# Micromouse_1_2.net
KiCad netlist of a schematic drawn in Altium Designer
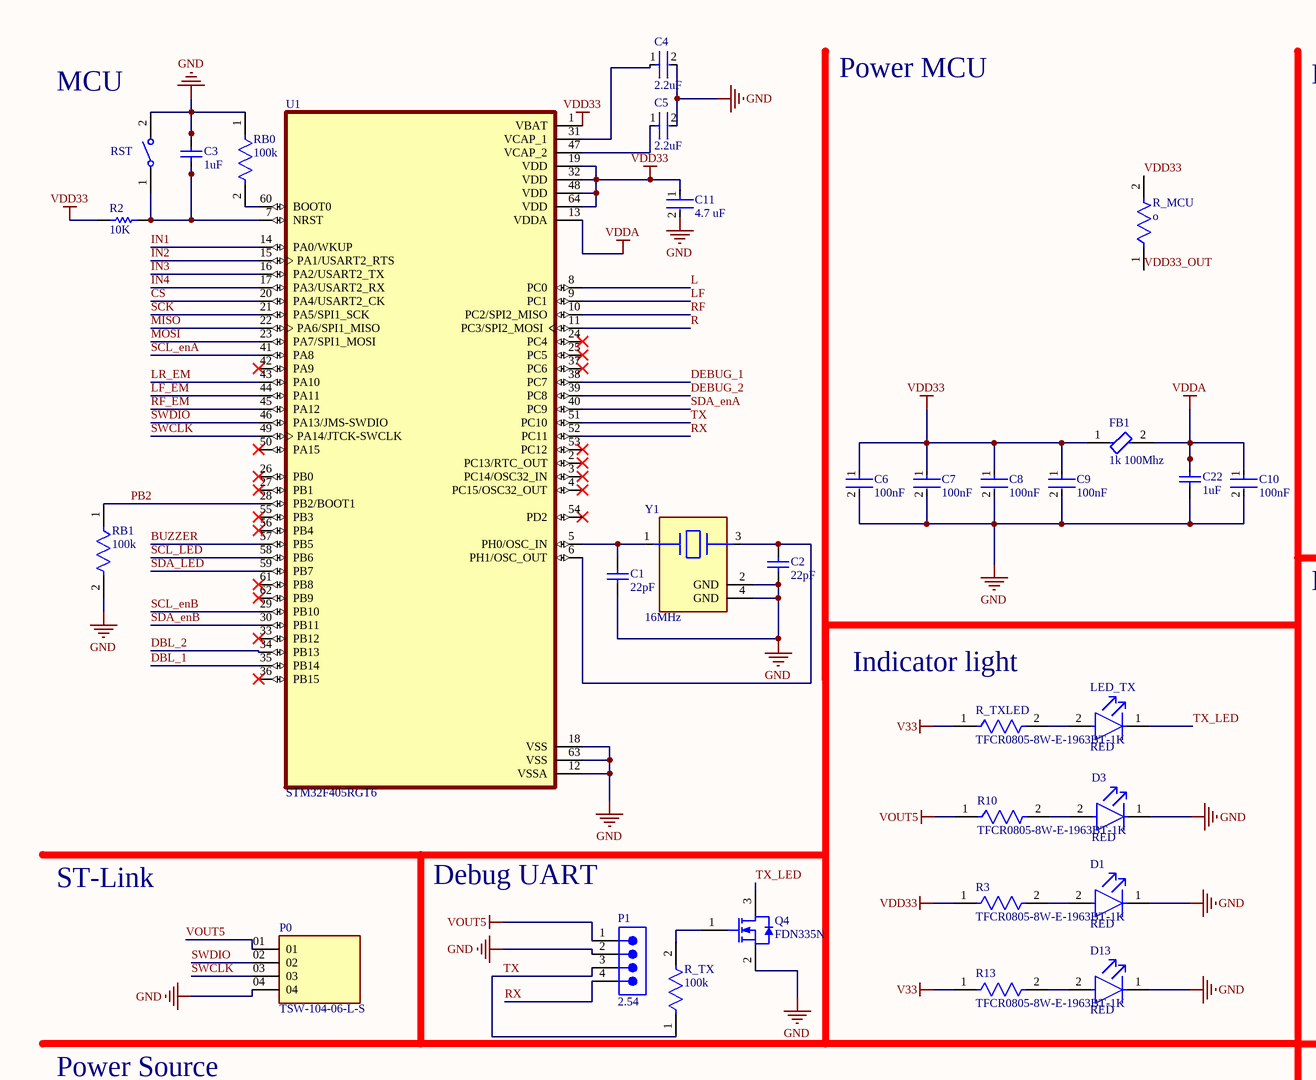
[diagram p0: Micromouse_1_2.SchDoc, top left]
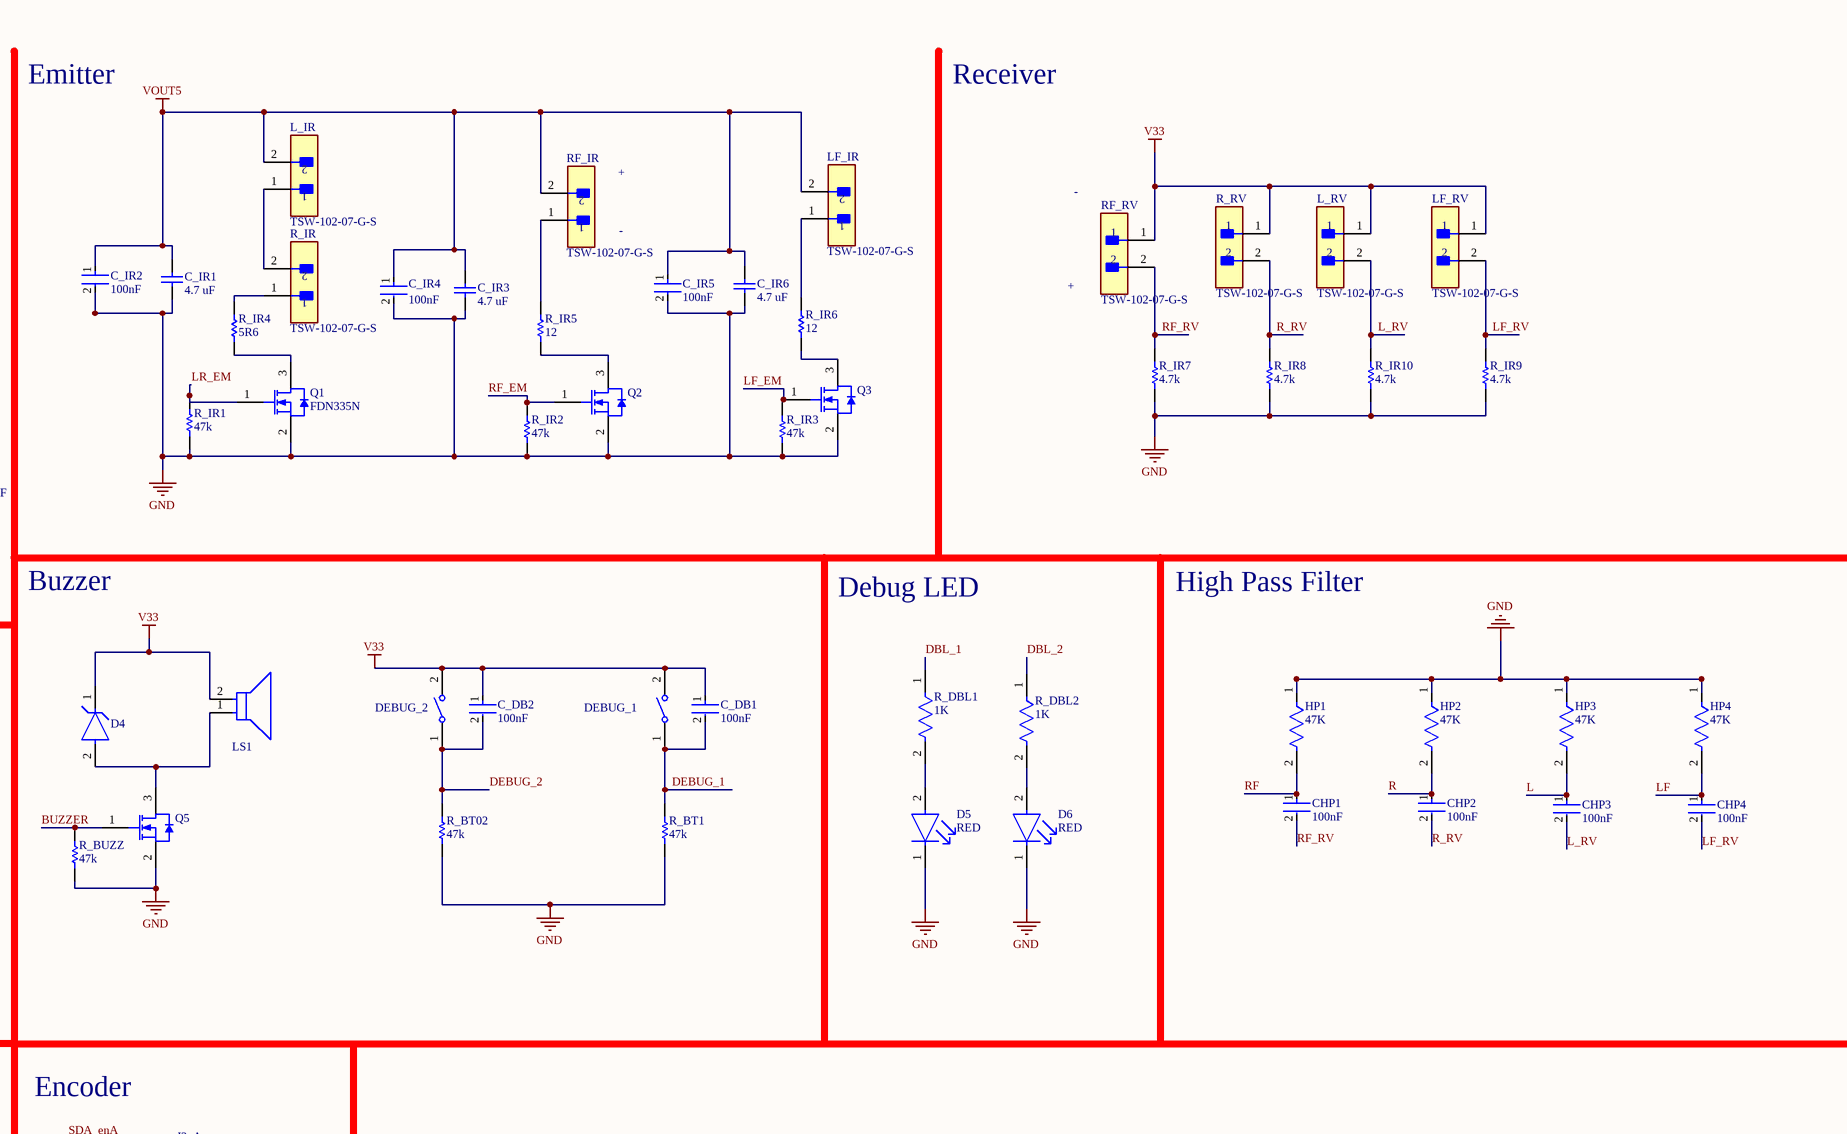
[diagram p1: Micromouse_1_2.SchDoc, top right]
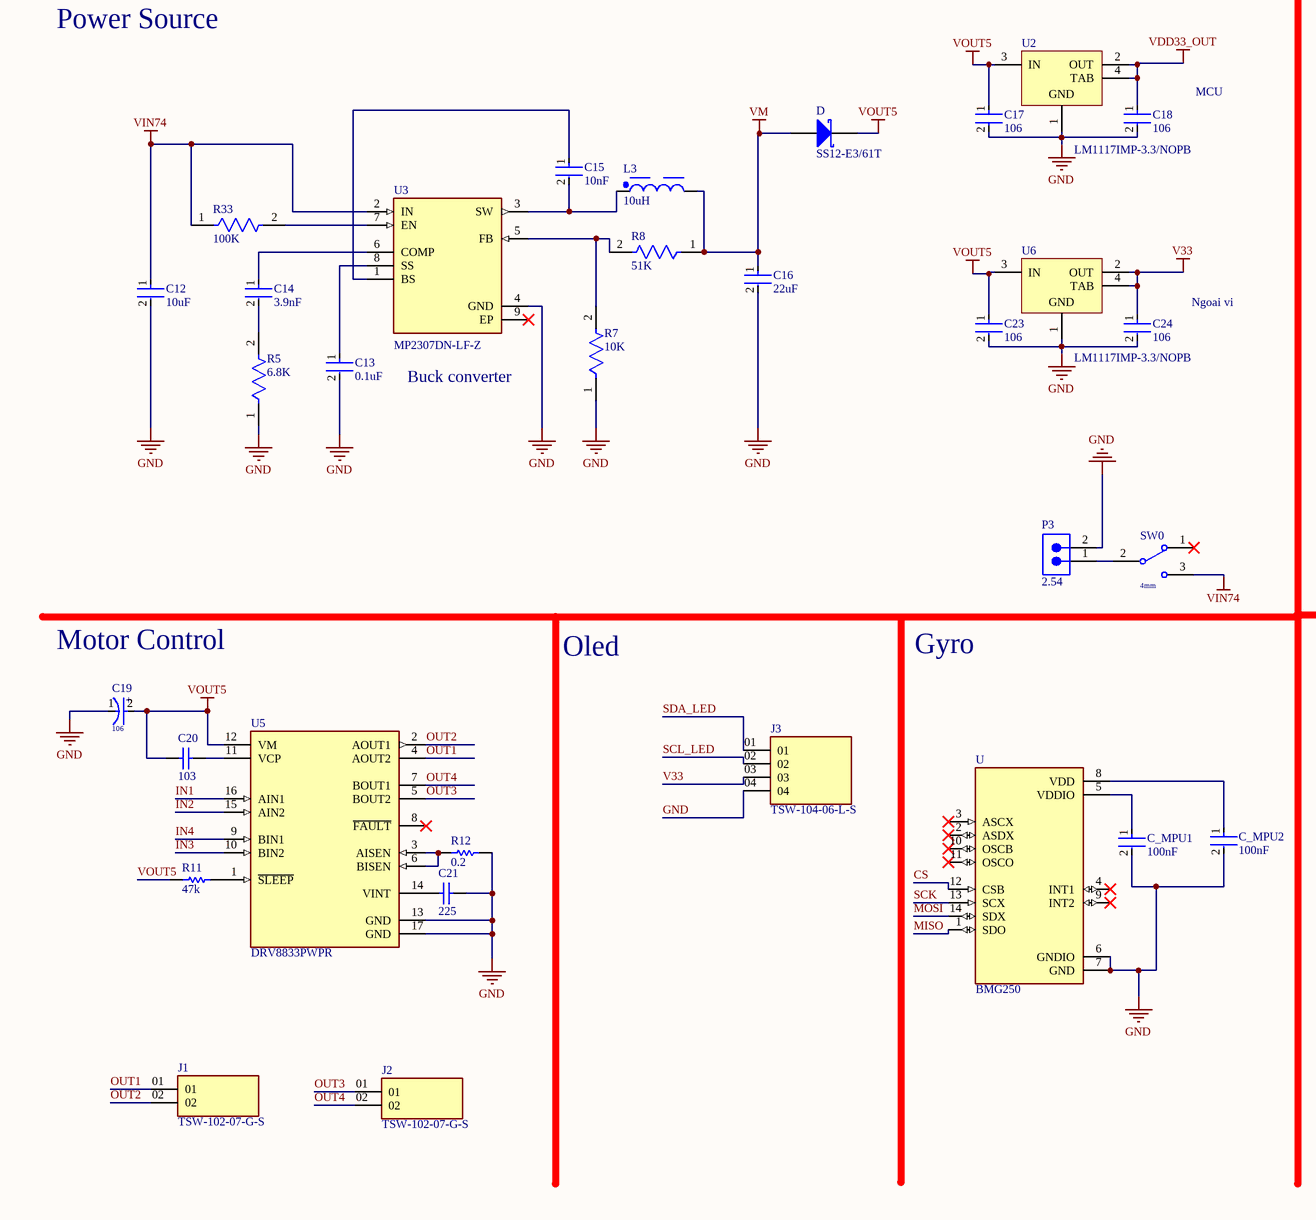
[diagram p2: Micromouse_1_2.SchDoc, bottom left]
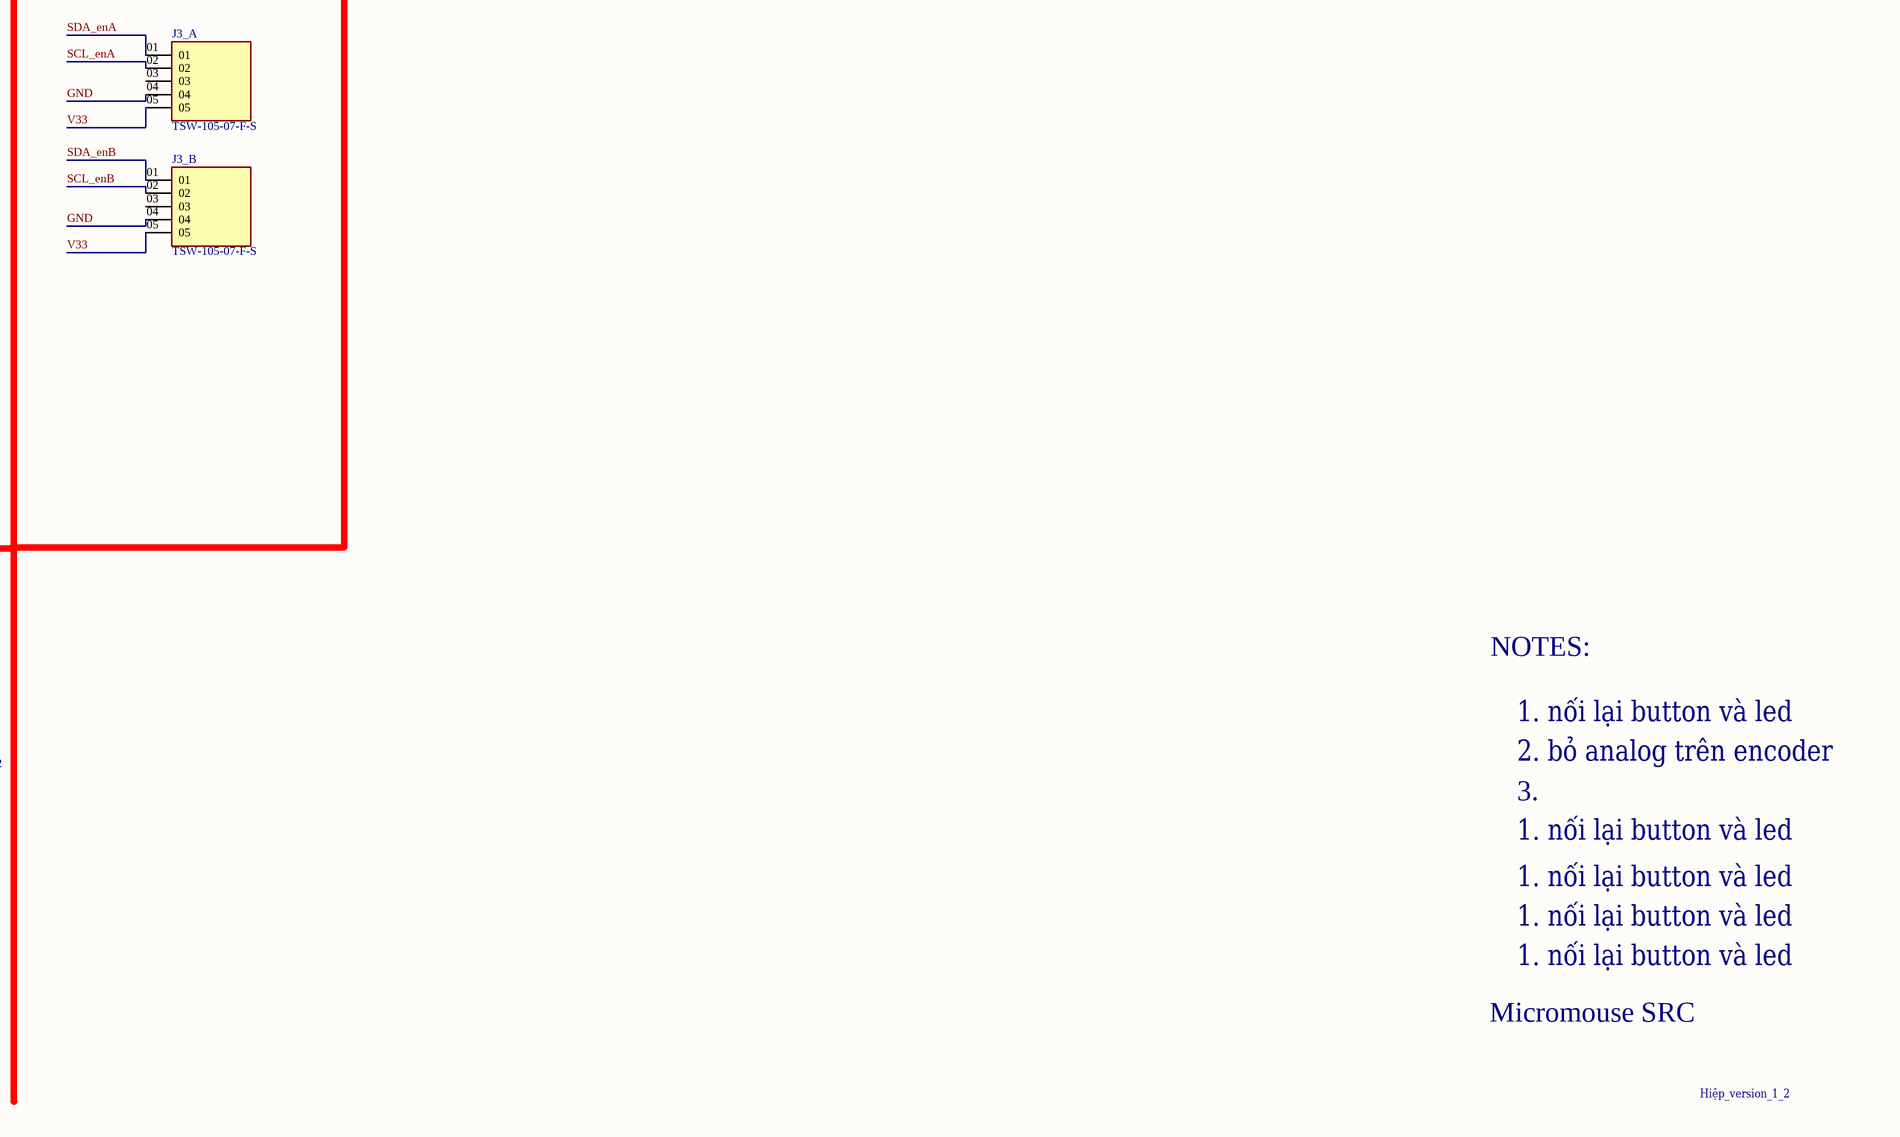
[diagram p3: Micromouse_1_2.SchDoc, bottom right]

(export (version "E")
  (design (tool "Eeschema 10.0.6"))
  (components
    (comp (ref "C1")
      (value "22pF")
      (footprint "CAPC1608X92X38ML15T08")
      (fields (field (name "PART NUMBER") "VJ0603A220FXBAC") (field (name "MANUFACTURER") "Vitramon"))
      (libsource (lib "Altium Content Vault") (part "CAP"))
    )
    (comp (ref "C2")
      (value "22pF")
      (footprint "CAPC1608X92X38ML15T08")
      (fields (field (name "PART NUMBER") "VJ0603A220FXBAC") (field (name "MANUFACTURER") "Vitramon"))
      (libsource (lib "Altium Content Vault") (part "CAP"))
    )
    (comp (ref "C3")
      (value "1uF")
      (footprint "CAPC1608X90X35NL15T15")
      (fields
        (field (name "PART NUMBER") "0603YD105MAT2A")
        (field (name "MANUFACTURER") "AVX Interconnect / Elco")
      )
      (libsource (lib "Altium Content Vault") (part "CAP"))
    )
    (comp (ref "C4")
      (value "2.2uF")
      (footprint "FP-CL21-IPC_B")
      (description "CL21 Series 0805 2.2uF 16V -20/+80% Tolerance Y5V Multilayer Ceramic Chip Capacitor")
      (fields (field (name "TOLERANCE") "80%") (field (name "VOLTAGE") "10V"))
      (libsource (lib "Altium Content Vault") (part "b4654b650e69147ec39a6b967a45e02"))
    )
    (comp (ref "C5")
      (value "2.2uF")
      (footprint "FP-CL21-IPC_B")
      (description "CL21 Series 0805 2.2uF 16V -20/+80% Tolerance Y5V Multilayer Ceramic Chip Capacitor")
      (fields (field (name "TOLERANCE") "80%") (field (name "VOLTAGE") "10V"))
      (libsource (lib "Altium Content Vault") (part "b4654b650e69147ec39a6b967a45e02"))
    )
    (comp (ref "C6")
      (value "100nF")
      (footprint "FP-CL10-IPC_C")
      (description "Cap Ceramic 100nF 25V X7R ±10% Pad SMD 0603 +125°C T/R")
      (fields (field (name "TOLERANCE") "10%"))
      (libsource (lib "Altium Content Vault") (part "b4654b650e69147ec39a6b967a45e02"))
    )
    (comp (ref "C7")
      (value "100nF")
      (footprint "FP-CL10-IPC_C")
      (description "Cap Ceramic 100nF 25V X7R ±10% Pad SMD 0603 +125°C T/R")
      (fields (field (name "TOLERANCE") "10%"))
      (libsource (lib "Altium Content Vault") (part "b4654b650e69147ec39a6b967a45e02"))
    )
    (comp (ref "C8")
      (value "100nF")
      (footprint "FP-CL10-IPC_C")
      (description "Cap Ceramic 100nF 25V X7R ±10% Pad SMD 0603 +125°C T/R")
      (fields (field (name "TOLERANCE") "10%"))
      (libsource (lib "Altium Content Vault") (part "b4654b650e69147ec39a6b967a45e02"))
    )
    (comp (ref "C9")
      (value "100nF")
      (footprint "FP-CL10-IPC_C")
      (description "Cap Ceramic 100nF 25V X7R ±10% Pad SMD 0603 +125°C T/R")
      (fields (field (name "TOLERANCE") "10%"))
      (libsource (lib "Altium Content Vault") (part "b4654b650e69147ec39a6b967a45e02"))
    )
    (comp (ref "C10")
      (value "100nF")
      (footprint "FP-CL10-IPC_C")
      (description "Cap Ceramic 100nF 25V X7R ±10% Pad SMD 0603 +125°C T/R")
      (fields (field (name "TOLERANCE") "10%"))
      (libsource (lib "Altium Content Vault") (part "b4654b650e69147ec39a6b967a45e02"))
    )
    (comp (ref "C11")
      (value "4.7 uF")
      (footprint "FP-C0603-CG-MFG")
      (description "CAP CER 4.7UF 6.3V X5R 0603")
      (fields (field (name "TOLERANCE") "10%") (field (name "MANUFACTURER") "Kemet"))
      (libsource (lib "Altium Content Vault") (part "11868f565c42a9108669ba33697ecf6"))
    )
    (comp (ref "C12")
      (value "10uF")
      (footprint "FP-C1206C-EB-MFG")
      (description "C1206 10 uF C0G 5.00% 50 V")
      (fields
        (field (name "MANUFACTURER PART NUMBER") "C1206C100J5GAC")
        (field (name "MANUFACTURER") "KEMET")
      )
      (libsource (lib "Altium Content Vault") (part "b4654b650e69147ec39a6b967a45e02"))
    )
    (comp (ref "C13")
      (value "0.1uF")
      (footprint "FP-C1206C-EB-MFG")
      (description "C1206 10 pF C0G 5.00% 50 V")
      (fields
        (field (name "MANUFACTURER PART NUMBER") "C1206C100J5GAC")
        (field (name "MANUFACTURER") "KEMET")
      )
      (libsource (lib "Altium Content Vault") (part "b4654b650e69147ec39a6b967a45e02"))
    )
    (comp (ref "C14")
      (value "3.9nF")
      (footprint "FP-C1206C-EB-MFG")
      (description "C1206 4.8nF C0G 5.00% 50 V")
      (fields
        (field (name "MANUFACTURER PART NUMBER") "C1206C100J5GAC")
        (field (name "MANUFACTURER") "KEMET")
      )
      (libsource (lib "Altium Content Vault") (part "b4654b650e69147ec39a6b967a45e02"))
    )
    (comp (ref "C15")
      (value "10nF")
      (footprint "FP-C1206C-EB-MFG")
      (description "C1206 10 pF C0G 5.00% 50 V")
      (fields
        (field (name "MANUFACTURER PART NUMBER") "C1206C100J5GAC")
        (field (name "MANUFACTURER") "KEMET")
      )
      (libsource (lib "Altium Content Vault") (part "b4654b650e69147ec39a6b967a45e02"))
    )
    (comp (ref "C16")
      (value "22uF")
      (footprint "FP-C1206C-EB-MFG")
      (description "C1206 10 pF C0G 5.00% 50 V")
      (fields
        (field (name "MANUFACTURER PART NUMBER") "C1206C100J5GAC")
        (field (name "MANUFACTURER") "KEMET")
      )
      (libsource (lib "Altium Content Vault") (part "b4654b650e69147ec39a6b967a45e02"))
    )
    (comp (ref "C17")
      (value "106")
      (footprint "FP-GRT31C-0_2-IPC_A")
      (description "Multi-Layer Ceramic Capacitor 10uF 50V X5R ±10% 1206 Emboss T/R")
      (fields (field (name "TOLERANCE") "10%"))
      (libsource (lib "Altium Content Vault") (part "02cd4be3c70576c341d710602a673aa"))
    )
    (comp (ref "C18")
      (value "106")
      (footprint "FP-GRT31C-0_2-IPC_A")
      (description "Multi-Layer Ceramic Capacitor 10uF 50V X5R ±10% 1206 Emboss T/R")
      (fields (field (name "TOLERANCE") "10%"))
      (libsource (lib "Altium Content Vault") (part "02cd4be3c70576c341d710602a673aa"))
    )
    (comp (ref "C19")
      (value "106")
      (footprint "FP-T491C-MFG")
      (description "CAP TANT 10UF 10% 25V 2312")
      (fields (field (name "TOLERANCE") "10%") (field (name "MANUFACTURER PART NUMBER") "T491C106K025AT"))
      (libsource (lib "Altium Content Vault") (part "203bc49f2ac43e59fd269a8c329ed05"))
    )
    (comp (ref "C20")
      (value "103")
      (footprint "CAPC2013X88X50LL20T25")
      (fields (field (name "MANUFACTURER") "Kemet") (field (name "PART NUMBER") "C0805C103K5RACTU"))
      (libsource (lib "Altium Content Vault") (part "CAP"))
    )
    (comp (ref "C21")
      (value "225")
      (footprint "CAPC3216X180X50LL20T25")
      (description "Chip Capacitor, 2.2 uF, +/- 10%, 50 V, -55 to 125 degC, 1206 (3216 Metric), RoHS, Tape and Reel")
      (fields (field (name "MANUFACTURER") "Kemet") (field (name "TOLERANCE") "10%"))
      (libsource (lib "Altium Content Vault") (part "CAP-NP-2"))
    )
    (comp (ref "C22")
      (value "1uF")
      (footprint "CAPC1608X90X35NL15T15")
      (fields
        (field (name "PART NUMBER") "0603YD105MAT2A")
        (field (name "MANUFACTURER") "AVX Interconnect / Elco")
      )
      (libsource (lib "Altium Content Vault") (part "CAP"))
    )
    (comp (ref "C23")
      (value "106")
      (footprint "FP-GRT31C-0_2-IPC_A")
      (description "Multi-Layer Ceramic Capacitor 10uF 50V X5R ±10% 1206 Emboss T/R")
      (fields (field (name "TOLERANCE") "10%"))
      (libsource (lib "Altium Content Vault") (part "02cd4be3c70576c341d710602a673aa"))
    )
    (comp (ref "C24")
      (value "106")
      (footprint "FP-GRT31C-0_2-IPC_A")
      (description "Multi-Layer Ceramic Capacitor 10uF 50V X5R ±10% 1206 Emboss T/R")
      (fields (field (name "TOLERANCE") "10%"))
      (libsource (lib "Altium Content Vault") (part "02cd4be3c70576c341d710602a673aa"))
    )
    (comp (ref "CHP1")
      (value "100nF")
      (footprint "FP-CL10-IPC_C")
      (description "Cap Ceramic 100nF 25V X7R ±10% Pad SMD 0603 +125°C T/R")
      (fields (field (name "TOLERANCE") "10%"))
      (libsource (lib "Altium Content Vault") (part "b4654b650e69147ec39a6b967a45e02"))
    )
    (comp (ref "CHP2")
      (value "100nF")
      (footprint "FP-CL10-IPC_C")
      (description "Cap Ceramic 100nF 25V X7R ±10% Pad SMD 0603 +125°C T/R")
      (fields (field (name "TOLERANCE") "10%"))
      (libsource (lib "Altium Content Vault") (part "b4654b650e69147ec39a6b967a45e02"))
    )
    (comp (ref "CHP3")
      (value "100nF")
      (footprint "FP-CL10-IPC_C")
      (description "Cap Ceramic 100nF 25V X7R ±10% Pad SMD 0603 +125°C T/R")
      (fields (field (name "TOLERANCE") "10%"))
      (libsource (lib "Altium Content Vault") (part "b4654b650e69147ec39a6b967a45e02"))
    )
    (comp (ref "CHP4")
      (value "100nF")
      (footprint "FP-CL10-IPC_C")
      (description "Cap Ceramic 100nF 25V X7R ±10% Pad SMD 0603 +125°C T/R")
      (fields (field (name "TOLERANCE") "10%"))
      (libsource (lib "Altium Content Vault") (part "b4654b650e69147ec39a6b967a45e02"))
    )
    (comp (ref "C_DB1")
      (value "100nF")
      (footprint "FP-CL10-IPC_C")
      (description "Cap Ceramic 100nF 25V X7R ±10% Pad SMD 0603 +125°C T/R")
      (fields (field (name "TOLERANCE") "10%"))
      (libsource (lib "Altium Content Vault") (part "b4654b650e69147ec39a6b967a45e02"))
    )
    (comp (ref "C_DB2")
      (value "100nF")
      (footprint "FP-CL10-IPC_C")
      (description "Cap Ceramic 100nF 25V X7R ±10% Pad SMD 0603 +125°C T/R")
      (fields (field (name "TOLERANCE") "10%"))
      (libsource (lib "Altium Content Vault") (part "b4654b650e69147ec39a6b967a45e02"))
    )
    (comp (ref "C_IR1")
      (value "4.7 uF")
      (footprint "CAPC2013X145X48ML20T23")
      (fields (field (name "MANUFACTURER") "Vitramon") (field (name "PART NUMBER") "VJ0805Y682KXAMT"))
      (libsource (lib "Altium Content Vault") (part "CAP"))
    )
    (comp (ref "C_IR2")
      (value "100nF")
      (footprint "FP-CL10-IPC_C")
      (description "Cap Ceramic 100nF 25V X7R ±10% Pad SMD 0603 +125°C T/R")
      (fields (field (name "TOLERANCE") "10%"))
      (libsource (lib "Altium Content Vault") (part "b4654b650e69147ec39a6b967a45e02"))
    )
    (comp (ref "C_IR3")
      (value "4.7 uF")
      (footprint "CAPC2013X145X48ML20T23")
      (fields (field (name "MANUFACTURER") "Vitramon") (field (name "PART NUMBER") "VJ0805Y682KXAMT"))
      (libsource (lib "Altium Content Vault") (part "CAP"))
    )
    (comp (ref "C_IR4")
      (value "100nF")
      (footprint "FP-CL10-IPC_C")
      (description "Cap Ceramic 100nF 25V X7R ±10% Pad SMD 0603 +125°C T/R")
      (fields (field (name "TOLERANCE") "10%"))
      (libsource (lib "Altium Content Vault") (part "b4654b650e69147ec39a6b967a45e02"))
    )
    (comp (ref "C_IR5")
      (value "100nF")
      (footprint "FP-CL10-IPC_C")
      (description "Cap Ceramic 100nF 25V X7R ±10% Pad SMD 0603 +125°C T/R")
      (fields (field (name "TOLERANCE") "10%"))
      (libsource (lib "Altium Content Vault") (part "b4654b650e69147ec39a6b967a45e02"))
    )
    (comp (ref "C_IR6")
      (value "4.7 uF")
      (footprint "CAPC2013X145X48ML20T23")
      (fields (field (name "MANUFACTURER") "Vitramon") (field (name "PART NUMBER") "VJ0805Y682KXAMT"))
      (libsource (lib "Altium Content Vault") (part "CAP"))
    )
    (comp (ref "C_MPU1")
      (value "100nF")
      (footprint "FP-CL10-IPC_C")
      (description "Cap Ceramic 100nF 25V X7R ±10% Pad SMD 0603 +125°C T/R")
      (fields (field (name "TOLERANCE") "10%"))
      (libsource (lib "Altium Content Vault") (part "b4654b650e69147ec39a6b967a45e02"))
    )
    (comp (ref "C_MPU2")
      (value "100nF")
      (footprint "FP-CL10-IPC_C")
      (description "Cap Ceramic 100nF 25V X7R ±10% Pad SMD 0603 +125°C T/R")
      (fields (field (name "TOLERANCE") "10%"))
      (libsource (lib "Altium Content Vault") (part "b4654b650e69147ec39a6b967a45e02"))
    )
    (comp (ref "D")
      (value "SS12-E3/61T")
      (footprint "VISH-DO-214AC_V")
      (description "Schottky Barrier Rectifier, 20 V, 1 A, -65 to 150 degC, 2-Pin DO-214AC (SMA), RoHS, Tape and Reel")
      (fields (field (name "MANUFACTURER") "Vishay Semiconductor"))
      (libsource (lib "Nguyen Hai Son") (part "DSKY-AK-2"))
    )
    (comp (ref "D1")
      (value "RED")
      (footprint "FP-LTST-C190GKT-MFG")
      (description "LED GREEN CLEAR CHIP SMD")
      (fields (field (name "VOLTAGE") "2V"))
      (libsource (lib "Altium Content Vault") (part "8706943c75ba83719d021d2fdc84c58"))
    )
    (comp (ref "D3")
      (value "RED")
      (footprint "FP-LTST-C190GKT-MFG")
      (description "LED GREEN CLEAR CHIP SMD")
      (fields (field (name "VOLTAGE") "2V"))
      (libsource (lib "Altium Content Vault") (part "8706943c75ba83719d021d2fdc84c58"))
    )
    (comp (ref "D4")
      (value "MMSZ5232B")
      (footprint "FP-MA02A-MFG")
      (description "MMSZ5232B MMSZ523 Series 500 mW 5.6 V 10 mA SMT Half-Watt Zener Diode SOD-123")
      (fields (field (name "TOLERANCE") "5%"))
      (libsource (lib "Altium Content Vault") (part "f813f71cba58e380607f5dd3caf9714"))
    )
    (comp (ref "D5")
      (value "RED")
      (footprint "FP-LTST-C190GKT-MFG")
      (description "LED GREEN CLEAR CHIP SMD")
      (fields (field (name "VOLTAGE") "2V"))
      (libsource (lib "Altium Content Vault") (part "8706943c75ba83719d021d2fdc84c58"))
    )
    (comp (ref "D6")
      (value "RED")
      (footprint "FP-LTST-C190GKT-MFG")
      (description "LED GREEN CLEAR CHIP SMD")
      (fields (field (name "VOLTAGE") "2V"))
      (libsource (lib "Altium Content Vault") (part "8706943c75ba83719d021d2fdc84c58"))
    )
    (comp (ref "D13")
      (value "RED")
      (footprint "FP-LTST-C190GKT-MFG")
      (description "LED GREEN CLEAR CHIP SMD")
      (fields (field (name "VOLTAGE") "2V"))
      (libsource (lib "Altium Content Vault") (part "8706943c75ba83719d021d2fdc84c58"))
    )
    (comp (ref "DEBUG_1")
      (value "~")
      (footprint "TECO-FSMSMTR_V")
      (description "FSMSM Push Button Switch, 50 mA, -35 to 85 degC, 2-Pin SMD, RoHS, Tape and Reel")
      (fields (field (name "MANUFACTURER") "TE Connectivity"))
      (libsource (lib "Altium Content Vault") (part "SW-SPST-2_C"))
    )
    (comp (ref "DEBUG_2")
      (value "~")
      (footprint "TECO-FSMSMTR_V")
      (description "FSMSM Push Button Switch, 50 mA, -35 to 85 degC, 2-Pin SMD, RoHS, Tape and Reel")
      (fields (field (name "MANUFACTURER") "TE Connectivity"))
      (libsource (lib "Altium Content Vault") (part "SW-SPST-2_C"))
    )
    (comp (ref "FB1")
      (value "1k 100Mhz")
      (footprint "FP-BLM21-0_2-t0_85-e0_5-IPC_C")
      (description "Chip Ferrite Bead, 0805, 60Ω @ 100MHz, 0.02Ω, 25%, 1.9A")
      (libsource (lib "Altium Content Vault") (part "5f30dd21d616792df468990f7003faa"))
    )
    (comp (ref "HP1")
      (value "47K")
      (footprint "FP-CRCW0805-e3-IPC_A")
      (description "RES Thick Film, 1kΩ, 5%, 0.125W, 200ppm/°C, 0805")
      (fields (field (name "TOLERANCE") "5%"))
      (libsource (lib "Altium Content Vault") (part "1029c3af85768c4190bb7ad29bc67b5"))
    )
    (comp (ref "HP2")
      (value "47K")
      (footprint "FP-CRCW0805-e3-IPC_A")
      (description "RES Thick Film, 1kΩ, 5%, 0.125W, 200ppm/°C, 0805")
      (fields (field (name "TOLERANCE") "5%"))
      (libsource (lib "Altium Content Vault") (part "1029c3af85768c4190bb7ad29bc67b5"))
    )
    (comp (ref "HP3")
      (value "47K")
      (footprint "FP-CRCW0805-e3-IPC_A")
      (description "RES Thick Film, 1kΩ, 5%, 0.125W, 200ppm/°C, 0805")
      (fields (field (name "TOLERANCE") "5%"))
      (libsource (lib "Altium Content Vault") (part "1029c3af85768c4190bb7ad29bc67b5"))
    )
    (comp (ref "HP4")
      (value "47K")
      (footprint "FP-CRCW0805-e3-IPC_A")
      (description "RES Thick Film, 1kΩ, 5%, 0.125W, 200ppm/°C, 0805")
      (fields (field (name "TOLERANCE") "5%"))
      (libsource (lib "Altium Content Vault") (part "1029c3af85768c4190bb7ad29bc67b5"))
    )
    (comp (ref "J1")
      (value "TSW-102-07-G-S")
      (footprint "SAMTEC_TSW-102-07-G-S")
      (fields (field (name "MF") "Samtec"))
      (libsource (lib "TSW-102-07-G-S") (part "TSW-102-07-G-S"))
    )
    (comp (ref "J2")
      (value "TSW-102-07-G-S")
      (footprint "SAMTEC_TSW-102-07-G-S")
      (fields (field (name "MF") "Samtec"))
      (libsource (lib "TSW-102-07-G-S") (part "TSW-102-07-G-S"))
    )
    (comp (ref "J3")
      (value "TSW-104-06-L-S")
      (footprint "SAMTEC_TSW-104-06-L-S")
      (libsource (lib "Vũ Hiệp") (part "TSW-104-06-L-S"))
    )
    (comp (ref "J3_A")
      (value "TSW-105-07-F-S")
      (footprint "SAMTEC_TSW-105-07-F-S")
      (fields (field (name "MF") "Samtec"))
      (libsource (lib "Vũ Hiệp") (part "TSW-105-07-F-S"))
    )
    (comp (ref "J3_B")
      (value "TSW-105-07-F-S")
      (footprint "SAMTEC_TSW-105-07-F-S")
      (fields (field (name "MF") "Samtec"))
      (libsource (lib "Vũ Hiệp") (part "TSW-105-07-F-S"))
    )
    (comp (ref "L3")
      (value "10uH")
      (footprint "WE-TPC_5818")
      (fields (field (name "TOLERANCE") "30%"))
      (libsource (lib "Altium Content Vault") (part "Inductor - 2"))
    )
    (comp (ref "LED_TX")
      (value "RED")
      (footprint "FP-LTST-C190GKT-MFG")
      (description "LED GREEN CLEAR CHIP SMD")
      (fields (field (name "VOLTAGE") "2V"))
      (libsource (lib "Altium Content Vault") (part "8706943c75ba83719d021d2fdc84c58"))
    )
    (comp (ref "LF_IR")
      (value "TSW-102-07-G-S")
      (footprint "FP-TSW-102-07-G-S-MFG")
      (description "CONN HEADER VERT 2POS 2.54MM")
      (fields
        (field (name "MANUFACTURER") "Samtec")
        (field (name "OCTOPART") "https://octopart.com/tsw-102-07-g-s-samtec-272197")
      )
      (libsource (lib "") (part "3bc925449376181038e59eaffc5286c_1"))
    )
    (comp (ref "LF_RV")
      (value "TSW-102-07-G-S")
      (footprint "FP-TSW-102-07-G-S-MFG")
      (description "CONN HEADER VERT 2POS 2.54MM")
      (fields
        (field (name "MANUFACTURER") "Samtec")
        (field (name "OCTOPART") "https://octopart.com/tsw-102-07-g-s-samtec-272197")
      )
      (libsource (lib "Altium Content Vault") (part "3bc925449376181038e59eaffc5286c"))
    )
    (comp (ref "LS1")
      (value "MCKPX-G1203A-K4056")
      (footprint "FP-MCKPX-G1203A-K4056-MFG")
      (description "MAGNETIC BUZZER AND TRANSDUCER - More Details")
      (fields
        (field (name "MANUFACTURER") "Multicomp Pro")
        (field (name "OCTOPART") "https://octopart.com/mckpx-g1203a-k4056-multicomp-12157154")
      )
      (libsource (lib "Altium Content Vault") (part "1973c4b650225fd2ddacaff6b763965"))
    )
    (comp (ref "L_IR")
      (value "TSW-102-07-G-S")
      (footprint "FP-TSW-102-07-G-S-MFG")
      (description "CONN HEADER VERT 2POS 2.54MM")
      (fields
        (field (name "MANUFACTURER") "Samtec")
        (field (name "OCTOPART") "https://octopart.com/tsw-102-07-g-s-samtec-272197")
      )
      (libsource (lib "") (part "3bc925449376181038e59eaffc5286c_1"))
    )
    (comp (ref "L_RV")
      (value "TSW-102-07-G-S")
      (footprint "FP-TSW-102-07-G-S-MFG")
      (description "CONN HEADER VERT 2POS 2.54MM")
      (fields
        (field (name "MANUFACTURER") "Samtec")
        (field (name "OCTOPART") "https://octopart.com/tsw-102-07-g-s-samtec-272197")
      )
      (libsource (lib "Altium Content Vault") (part "3bc925449376181038e59eaffc5286c"))
    )
    (comp (ref "P0")
      (value "TSW-104-06-L-S")
      (footprint "SAMTEC_TSW-104-06-L-S")
      (libsource (lib "Vũ Hiệp") (part "TSW-104-06-L-S"))
    )
    (comp (ref "P1")
      (value "2.54")
      (footprint "61300411121")
      (libsource (lib "Altium Content Vault") (part "Header_Male_1R_04P"))
    )
    (comp (ref "P3")
      (value "2.54")
      (footprint "61300211121")
      (libsource (lib "Altium Content Vault") (part "Header_Male_1R_02P"))
    )
    (comp (ref "Q1")
      (value "FDN335N")
      (footprint "FAIR-SSOT3L-3_V")
      (fields (field (name "MANUFACTURER") "FairchildSemiconductor"))
      (libsource (lib "Altium Content Vault") (part "NEMOS-GSD-3"))
    )
    (comp (ref "Q2")
      (value "~")
      (footprint "FAIR-SSOT3L-3_V")
      (fields (field (name "MANUFACTURER") "FairchildSemiconductor"))
      (libsource (lib "Altium Content Vault") (part "NEMOS-GSD-3"))
    )
    (comp (ref "Q3")
      (value "~")
      (footprint "FAIR-SSOT3L-3_V")
      (fields (field (name "MANUFACTURER") "FairchildSemiconductor"))
      (libsource (lib "Altium Content Vault") (part "NEMOS-GSD-3"))
    )
    (comp (ref "Q4")
      (value "FDN335N")
      (footprint "FAIR-SSOT3L-3_V")
      (fields (field (name "MANUFACTURER") "FairchildSemiconductor"))
      (libsource (lib "Altium Content Vault") (part "NEMOS-GSD-3"))
    )
    (comp (ref "Q5")
      (value "~")
      (footprint "FAIR-SSOT3L-3_V")
      (fields (field (name "MANUFACTURER") "FairchildSemiconductor"))
      (libsource (lib "Altium Content Vault") (part "NEMOS-GSD-3"))
    )
    (comp (ref "R2")
      (value "10K")
      (footprint "RESC1206(3216)_M")
      (description "10K 0.25W 5% 1206 (3216 Metric)  SMD")
      (fields (field (name "POWER") "0.25 W") (field (name "TOLERANCE") "5 %"))
      (libsource (lib "Altium Content Vault") (part "RES"))
    )
    (comp (ref "R3")
      (value "TFCR0805-8W-E-1963BT-1K")
      (footprint "FP-TFCR0805-MFG")
      (description "RES Thin Film,  196kΩ, 0.1%, 0.125W, 25ppm/°C, 0805")
      (libsource (lib "Altium Content Vault") (part "1029c3af85768c4190bb7ad29bc67b5"))
    )
    (comp (ref "R5")
      (value "6.8K")
      (footprint "FP-CRCW0805-e3-IPC_B")
      (description "RES Thick Film, 2.49Ω, 1%, 0.125W, 200ppm/°C, 0805")
      (fields (field (name "TOLERANCE") "1%"))
      (libsource (lib "Altium Content Vault") (part "1029c3af85768c4190bb7ad29bc67b5"))
    )
    (comp (ref "R7")
      (value "10K")
      (footprint "FP-CRCW0805-e3-IPC_B")
      (description "RES Thick Film, 2.49Ω, 1%, 0.125W, 200ppm/°C, 0805")
      (fields (field (name "TOLERANCE") "1%"))
      (libsource (lib "Altium Content Vault") (part "1029c3af85768c4190bb7ad29bc67b5"))
    )
    (comp (ref "R8")
      (value "51K")
      (footprint "FP-CRCW0805-e3-IPC_B")
      (description "RES Thick Film, 2.49Ω, 1%, 0.125W, 200ppm/°C, 0805")
      (fields (field (name "TOLERANCE") "1%"))
      (libsource (lib "Altium Content Vault") (part "1029c3af85768c4190bb7ad29bc67b5"))
    )
    (comp (ref "R10")
      (value "TFCR0805-8W-E-1963BT-1K")
      (footprint "FP-TFCR0805-MFG")
      (description "RES Thin Film,  196kΩ, 0.1%, 0.125W, 25ppm/°C, 0805")
      (libsource (lib "Altium Content Vault") (part "1029c3af85768c4190bb7ad29bc67b5"))
    )
    (comp (ref "R11")
      (value "47k")
      (footprint "RESC3216X60X45LL10T20")
      (fields (field (name "PART NUMBER") "CRCW120647K0FKEA") (field (name "MANUFACTURER") "Vishay Dale"))
      (libsource (lib "Altium Content Vault") (part "RES"))
    )
    (comp (ref "R12")
      (value "0.2")
      (footprint "RESC3216X89X51ML25T25")
      (fields (field (name "MANUFACTURER") "Vishay Dale") (field (name "PART NUMBER") "WSL1206R2000FEA"))
      (libsource (lib "Altium Content Vault") (part "RES"))
    )
    (comp (ref "R13")
      (value "TFCR0805-8W-E-1963BT-1K")
      (footprint "FP-TFCR0805-MFG")
      (description "RES Thin Film,  196kΩ, 0.1%, 0.125W, 25ppm/°C, 0805")
      (libsource (lib "Altium Content Vault") (part "1029c3af85768c4190bb7ad29bc67b5"))
    )
    (comp (ref "R33")
      (value "100K")
      (footprint "FP-CRCW0805-e3-IPC_B")
      (description "RES Thick Film, 2.49Ω, 1%, 0.125W, 200ppm/°C, 0805")
      (fields (field (name "TOLERANCE") "1%"))
      (libsource (lib "Altium Content Vault") (part "1029c3af85768c4190bb7ad29bc67b5"))
    )
    (comp (ref "RB0")
      (value "100k")
      (footprint "FP-RC3216-IPC_C")
      (description "Res Thick Film 1206 10kΩ 5% 0.25W ±100ppm/°C Molded SMD T/R")
      (fields (field (name "TOLERANCE") "5%"))
      (libsource (lib "Altium Content Vault") (part "1029c3af85768c4190bb7ad29bc67b5"))
    )
    (comp (ref "RB1")
      (value "100k")
      (footprint "FP-RC3216-IPC_C")
      (description "Res Thick Film 1206 10kΩ 5% 0.25W ±100ppm/°C Molded SMD T/R")
      (fields (field (name "TOLERANCE") "5%"))
      (libsource (lib "Altium Content Vault") (part "1029c3af85768c4190bb7ad29bc67b5"))
    )
    (comp (ref "RF_IR")
      (value "TSW-102-07-G-S")
      (footprint "FP-TSW-102-07-G-S-MFG")
      (description "CONN HEADER VERT 2POS 2.54MM")
      (fields
        (field (name "MANUFACTURER") "Samtec")
        (field (name "OCTOPART") "https://octopart.com/tsw-102-07-g-s-samtec-272197")
      )
      (libsource (lib "") (part "3bc925449376181038e59eaffc5286c_1"))
    )
    (comp (ref "RF_RV")
      (value "TSW-102-07-G-S")
      (footprint "FP-TSW-102-07-G-S-MFG")
      (description "CONN HEADER VERT 2POS 2.54MM")
      (fields
        (field (name "MANUFACTURER") "Samtec")
        (field (name "OCTOPART") "https://octopart.com/tsw-102-07-g-s-samtec-272197")
      )
      (libsource (lib "Altium Content Vault") (part "3bc925449376181038e59eaffc5286c"))
    )
    (comp (ref "RST")
      (value "~")
      (footprint "TECO-FSMSMTR_V")
      (description "FSMSM Push Button Switch, 50 mA, -35 to 85 degC, 2-Pin SMD, RoHS, Tape and Reel")
      (fields (field (name "MANUFACTURER") "TE Connectivity"))
      (libsource (lib "Altium Content Vault") (part "SW-SPST-2_C"))
    )
    (comp (ref "R_BT1")
      (value "47k")
      (footprint "RESC2013X60X35NL10T20")
      (description "Chip Resistor, 47 KOhm, +/- 1%, 0.125 W, -55 to 155 degC, 0805 (2012 Metric), RoHS, Tape and Reel")
      (fields (field (name "MANUFACTURER") "Yageo"))
      (libsource (lib "Altium Content Vault") (part "RES-2"))
    )
    (comp (ref "R_BT02")
      (value "47k")
      (footprint "RESC2013X60X35NL10T20")
      (description "Chip Resistor, 47 KOhm, +/- 1%, 0.125 W, -55 to 155 degC, 0805 (2012 Metric), RoHS, Tape and Reel")
      (fields (field (name "MANUFACTURER") "Yageo"))
      (libsource (lib "Altium Content Vault") (part "RES-2"))
    )
    (comp (ref "R_BUZZ")
      (value "47k")
      (footprint "RESC2013X60X35NL10T20")
      (description "Chip Resistor, 47 KOhm, +/- 1%, 0.125 W, -55 to 155 degC, 0805 (2012 Metric), RoHS, Tape and Reel")
      (fields (field (name "MANUFACTURER") "Yageo"))
      (libsource (lib "Altium Content Vault") (part "RES-2"))
    )
    (comp (ref "R_DBL1")
      (value "1K")
      (footprint "FP-CRCW0805-e3-IPC_A")
      (description "RES Thick Film, 1kΩ, 5%, 0.125W, 200ppm/°C, 0805")
      (fields (field (name "TOLERANCE") "5%"))
      (libsource (lib "Altium Content Vault") (part "1029c3af85768c4190bb7ad29bc67b5"))
    )
    (comp (ref "R_DBL2")
      (value "1K")
      (footprint "FP-CRCW0805-e3-IPC_A")
      (description "RES Thick Film, 1kΩ, 5%, 0.125W, 200ppm/°C, 0805")
      (fields (field (name "TOLERANCE") "5%"))
      (libsource (lib "Altium Content Vault") (part "1029c3af85768c4190bb7ad29bc67b5"))
    )
    (comp (ref "R_IR")
      (value "TSW-102-07-G-S")
      (footprint "FP-TSW-102-07-G-S-MFG")
      (description "CONN HEADER VERT 2POS 2.54MM")
      (fields
        (field (name "MANUFACTURER") "Samtec")
        (field (name "OCTOPART") "https://octopart.com/tsw-102-07-g-s-samtec-272197")
      )
      (libsource (lib "") (part "3bc925449376181038e59eaffc5286c_1"))
    )
    (comp (ref "R_IR1")
      (value "47k")
      (footprint "RESC2013X60X35NL10T20")
      (description "Chip Resistor, 47 KOhm, +/- 1%, 0.125 W, -55 to 155 degC, 0805 (2012 Metric), RoHS, Tape and Reel")
      (fields (field (name "MANUFACTURER") "Yageo"))
      (libsource (lib "Altium Content Vault") (part "RES-2"))
    )
    (comp (ref "R_IR2")
      (value "47k")
      (footprint "RESC2013X60X35NL10T20")
      (description "Chip Resistor, 47 KOhm, +/- 1%, 0.125 W, -55 to 155 degC, 0805 (2012 Metric), RoHS, Tape and Reel")
      (fields (field (name "MANUFACTURER") "Yageo"))
      (libsource (lib "Altium Content Vault") (part "RES-2"))
    )
    (comp (ref "R_IR3")
      (value "47k")
      (footprint "RESC2013X60X35NL10T20")
      (description "Chip Resistor, 47 KOhm, +/- 1%, 0.125 W, -55 to 155 degC, 0805 (2012 Metric), RoHS, Tape and Reel")
      (fields (field (name "MANUFACTURER") "Yageo"))
      (libsource (lib "Altium Content Vault") (part "RES-2"))
    )
    (comp (ref "R_IR4")
      (value "5R6")
      (footprint "RESC2013X50X30NL20T20")
      (fields (field (name "MANUFACTURER") "Vishay Dale") (field (name "PART NUMBER") "CRCW080510R0FKEA"))
      (libsource (lib "Altium Content Vault") (part "RES"))
    )
    (comp (ref "R_IR5")
      (value "12")
      (footprint "RESC2013X50X30NL20T20")
      (fields (field (name "MANUFACTURER") "Vishay Dale") (field (name "PART NUMBER") "CRCW080510R0FKEA"))
      (libsource (lib "Altium Content Vault") (part "RES"))
    )
    (comp (ref "R_IR6")
      (value "12")
      (footprint "RESC2013X50X30NL20T20")
      (fields (field (name "MANUFACTURER") "Vishay Dale") (field (name "PART NUMBER") "CRCW080510R0FKEA"))
      (libsource (lib "Altium Content Vault") (part "RES"))
    )
    (comp (ref "R_IR7")
      (value "4.7k")
      (footprint "YAGO-RC0805_M")
      (fields
        (field (name "TOLERANCE") "+/- 1%")
        (field (name "PARTNUMBER") "RC0805FR-074K7L")
        (field (name "POWER") "0.125 W")
      )
      (libsource (lib "Altium Content Vault") (part "YAGO-RES-2"))
    )
    (comp (ref "R_IR8")
      (value "4.7k")
      (footprint "YAGO-RC0805_M")
      (fields
        (field (name "TOLERANCE") "+/- 1%")
        (field (name "PARTNUMBER") "RC0805FR-074K7L")
        (field (name "POWER") "0.125 W")
      )
      (libsource (lib "Altium Content Vault") (part "YAGO-RES-2"))
    )
    (comp (ref "R_IR9")
      (value "4.7k")
      (footprint "YAGO-RC0805_M")
      (fields
        (field (name "TOLERANCE") "+/- 1%")
        (field (name "PARTNUMBER") "RC0805FR-074K7L")
        (field (name "POWER") "0.125 W")
      )
      (libsource (lib "Altium Content Vault") (part "YAGO-RES-2"))
    )
    (comp (ref "R_IR10")
      (value "4.7k")
      (footprint "YAGO-RC0805_M")
      (fields
        (field (name "TOLERANCE") "+/- 1%")
        (field (name "PARTNUMBER") "RC0805FR-074K7L")
        (field (name "POWER") "0.125 W")
      )
      (libsource (lib "Altium Content Vault") (part "YAGO-RES-2"))
    )
    (comp (ref "R_MCU")
      (value "o")
      (footprint "FP-TFCR0805-MFG")
      (description "RES Thin Film,  196kΩ, 0.1%, 0.125W, 25ppm/°C, 0805")
      (libsource (lib "Altium Content Vault") (part "1029c3af85768c4190bb7ad29bc67b5"))
    )
    (comp (ref "R_RV")
      (value "TSW-102-07-G-S")
      (footprint "FP-TSW-102-07-G-S-MFG")
      (description "CONN HEADER VERT 2POS 2.54MM")
      (fields
        (field (name "MANUFACTURER") "Samtec")
        (field (name "OCTOPART") "https://octopart.com/tsw-102-07-g-s-samtec-272197")
      )
      (libsource (lib "Altium Content Vault") (part "3bc925449376181038e59eaffc5286c"))
    )
    (comp (ref "R_TX")
      (value "100k")
      (footprint "FP-TFCR0805-MFG")
      (description "RES Thin Film,  196kΩ, 0.1%, 0.125W, 25ppm/°C, 0805")
      (libsource (lib "Altium Content Vault") (part "1029c3af85768c4190bb7ad29bc67b5"))
    )
    (comp (ref "R_TXLED")
      (value "TFCR0805-8W-E-1963BT-1K")
      (footprint "FP-TFCR0805-MFG")
      (description "RES Thin Film,  196kΩ, 0.1%, 0.125W, 25ppm/°C, 0805")
      (libsource (lib "Altium Content Vault") (part "1029c3af85768c4190bb7ad29bc67b5"))
    )
    (comp (ref "SW0")
      (value "4mm")
      (footprint "ESWI-EG1218_V")
      (description "Slide Switch, 500 V, -20 to 70 degC, 3-Pin THD, RoHS")
      (libsource (lib "Altium Content Vault") (part "SW-SPDT-3_B"))
    )
    (comp (ref "U")
      (value "BMG250")
      (footprint "XDCR_BMG250")
      (description "Gyroscope X _Pitch_, Y _Roll_, Z _Yaw_ Â±125, 250, 500, 1000, 2000 25Hz ~ 3200Hz IÂ²C, SPI")
      (fields (field (name "MF") "Bosch"))
      (libsource (lib "BMG250") (part "BMG250"))
    )
    (comp (ref "U1")
      (value "STM32F405RGT6")
      (footprint "QFP50P1200X1200X160-64N")
      (fields (field (name "MF") "STMicroelectronics"))
      (libsource (lib "Vũ Hiệp") (part "STM32F405RGT6"))
    )
    (comp (ref "U2")
      (value "LM1117IMP-3.3/NOPB")
      (footprint "DCY0004A_N")
      (description "800mA Low-Dropout Linear Regulator, 4-pin SOT-223, Pb-Free")
      (fields (field (name "MANUFACTURER") "Texas Instruments"))
      (libsource (lib "Altium Content Vault") (part "PM-REG-LM1086-SOT4"))
    )
    (comp (ref "U3")
      (value "MP2307DN-LF-Z")
      (footprint "SOIC127P600X170-9N")
      (fields (field (name "MF") "Monolithic Power"))
      (libsource (lib "MP2307DN-LF-Z") (part "MP2307DN-LF-Z"))
    )
    (comp (ref "U5")
      (value "DRV8833PWPR")
      (footprint "FP-PWP0016C-IPC_B")
      (description "IC MOTOR DRIVER PAR 16HTSSOP")
      (libsource (lib "Altium Content Vault") (part "bca689d78e207bdabf30b9b31c2f798"))
    )
    (comp (ref "U6")
      (value "LM1117IMP-3.3/NOPB")
      (footprint "DCY0004A_N")
      (description "800mA Low-Dropout Linear Regulator, 4-pin SOT-223, Pb-Free")
      (fields (field (name "MANUFACTURER") "Texas Instruments"))
      (libsource (lib "Altium Content Vault") (part "PM-REG-LM1086-SOT4"))
    )
    (comp (ref "Y1")
      (value "16MHz")
      (footprint "FP-ABM10W-MFG")
      (description "CRYSTAL 16.0000MHZ 4PF SMD")
      (libsource (lib "Altium Content Vault") (part "5d53a81b36bb19e40e9e80ec3e46f97"))
    )
  )
  (nets
    (net (code "1") (name "/BUZZER") (class "Default")
      (node (ref "Q5") (pin "1") (pinfunction "G_1") (pintype "passive"))
      (node (ref "R_BUZZ") (pin "2") (pinfunction "2_2") (pintype "passive"))
      (node (ref "U1") (pin "57") (pinfunction "PB5_57") (pintype "bidirectional"))
    )
    (net (code "2") (name "/CS") (class "Default")
      (node (ref "U") (pin "12") (pinfunction "CSB_12") (pintype "input"))
      (node (ref "U1") (pin "20") (pinfunction "PA4/USART2_CK_20") (pintype "bidirectional"))
    )
    (net (code "3") (name "/DBL_1") (class "Default")
      (node (ref "R_DBL1") (pin "1") (pinfunction "1_1") (pintype "passive"))
      (node (ref "U1") (pin "35") (pinfunction "PB14_35") (pintype "bidirectional"))
    )
    (net (code "4") (name "/DBL_2") (class "Default")
      (node (ref "R_DBL2") (pin "1") (pinfunction "1_1") (pintype "passive"))
      (node (ref "U1") (pin "34") (pinfunction "PB13_34") (pintype "bidirectional"))
    )
    (net (code "5") (name "/DEBUG_1") (class "Default")
      (node (ref "C_DB1") (pin "2") (pinfunction "2_2") (pintype "passive"))
      (node (ref "DEBUG_1") (pin "1") (pinfunction "1_1") (pintype "passive"))
      (node (ref "R_BT1") (pin "2") (pinfunction "2_2") (pintype "passive"))
      (node (ref "U1") (pin "38") (pinfunction "PC7_38") (pintype "bidirectional"))
    )
    (net (code "6") (name "/DEBUG_2") (class "Default")
      (node (ref "C_DB2") (pin "2") (pinfunction "2_2") (pintype "passive"))
      (node (ref "DEBUG_2") (pin "1") (pinfunction "1_1") (pintype "passive"))
      (node (ref "R_BT02") (pin "2") (pinfunction "2_2") (pintype "passive"))
      (node (ref "U1") (pin "39") (pinfunction "PC8_39") (pintype "bidirectional"))
    )
    (net (code "7") (name "/IN1") (class "Default")
      (node (ref "U1") (pin "14") (pinfunction "PA0/WKUP_14") (pintype "bidirectional"))
      (node (ref "U5") (pin "16") (pinfunction "AIN1_16") (pintype "input"))
    )
    (net (code "8") (name "/IN2") (class "Default")
      (node (ref "U1") (pin "15") (pinfunction "PA1/USART2_RTS_15") (pintype "bidirectional"))
      (node (ref "U5") (pin "15") (pinfunction "AIN2_15") (pintype "input"))
    )
    (net (code "9") (name "/IN3") (class "Default")
      (node (ref "U1") (pin "16") (pinfunction "PA2/USART2_TX_16") (pintype "bidirectional"))
      (node (ref "U5") (pin "10") (pinfunction "BIN2_10") (pintype "input"))
    )
    (net (code "10") (name "/IN4") (class "Default")
      (node (ref "U1") (pin "17") (pinfunction "PA3/USART2_RX_17") (pintype "bidirectional"))
      (node (ref "U5") (pin "9") (pinfunction "BIN1_9") (pintype "input"))
    )
    (net (code "11") (name "/L") (class "Default")
      (node (ref "CHP3") (pin "1") (pinfunction "1_1") (pintype "passive"))
      (node (ref "HP3") (pin "2") (pinfunction "2_2") (pintype "passive"))
      (node (ref "U1") (pin "8") (pinfunction "PC0_8") (pintype "bidirectional"))
    )
    (net (code "12") (name "/LF") (class "Default")
      (node (ref "CHP4") (pin "1") (pinfunction "1_1") (pintype "passive"))
      (node (ref "HP4") (pin "2") (pinfunction "2_2") (pintype "passive"))
      (node (ref "U1") (pin "9") (pinfunction "PC1_9") (pintype "bidirectional"))
    )
    (net (code "13") (name "/LF_EM") (class "Default")
      (node (ref "Q3") (pin "1") (pinfunction "G_1") (pintype "passive"))
      (node (ref "R_IR3") (pin "2") (pinfunction "2_2") (pintype "passive"))
      (node (ref "U1") (pin "44") (pinfunction "PA11_44") (pintype "bidirectional"))
    )
    (net (code "14") (name "/LF_RV") (class "Default")
      (node (ref "CHP4") (pin "2") (pinfunction "2_2") (pintype "passive"))
      (node (ref "LF_RV") (pin "2") (pinfunction "2_2") (pintype "passive"))
      (node (ref "R_IR9") (pin "2") (pinfunction "2_2") (pintype "passive"))
    )
    (net (code "15") (name "/LR_EM") (class "Default")
      (node (ref "Q1") (pin "1") (pinfunction "G_1") (pintype "passive"))
      (node (ref "R_IR1") (pin "2") (pinfunction "2_2") (pintype "passive"))
      (node (ref "U1") (pin "43") (pinfunction "PA10_43") (pintype "bidirectional"))
    )
    (net (code "16") (name "/L_RV") (class "Default")
      (node (ref "CHP3") (pin "2") (pinfunction "2_2") (pintype "passive"))
      (node (ref "L_RV") (pin "2") (pinfunction "2_2") (pintype "passive"))
      (node (ref "R_IR10") (pin "2") (pinfunction "2_2") (pintype "passive"))
    )
    (net (code "17") (name "/MISO") (class "Default")
      (node (ref "U") (pin "1") (pinfunction "SDO_1") (pintype "bidirectional"))
      (node (ref "U1") (pin "22") (pinfunction "PA6/SPI1_MISO_22") (pintype "bidirectional"))
    )
    (net (code "18") (name "/MOSI") (class "Default")
      (node (ref "U") (pin "14") (pinfunction "SDX_14") (pintype "bidirectional"))
      (node (ref "U1") (pin "23") (pinfunction "PA7/SPI1_MOSI_23") (pintype "bidirectional"))
    )
    (net (code "19") (name "/OUT1") (class "Default")
      (node (ref "J1") (pin "01") (pinfunction "01_01") (pintype "passive"))
      (node (ref "U5") (pin "4") (pinfunction "AOUT2_4") (pintype "tri_state"))
    )
    (net (code "20") (name "/OUT2") (class "Default")
      (node (ref "J1") (pin "02") (pinfunction "02_02") (pintype "passive"))
      (node (ref "U5") (pin "2") (pinfunction "AOUT1_2") (pintype "output"))
    )
    (net (code "21") (name "/OUT3") (class "Default")
      (node (ref "J2") (pin "01") (pinfunction "01_01") (pintype "passive"))
      (node (ref "U5") (pin "5") (pinfunction "BOUT2_5") (pintype "tri_state"))
    )
    (net (code "22") (name "/OUT4") (class "Default")
      (node (ref "J2") (pin "02") (pinfunction "02_02") (pintype "passive"))
      (node (ref "U5") (pin "7") (pinfunction "BOUT1_7") (pintype "tri_state"))
    )
    (net (code "23") (name "/PB2") (class "Default")
      (node (ref "RB1") (pin "1") (pinfunction "1_1") (pintype "passive"))
      (node (ref "U1") (pin "28") (pinfunction "PB2/BOOT1_28") (pintype "bidirectional"))
    )
    (net (code "24") (name "/R") (class "Default")
      (node (ref "CHP2") (pin "1") (pinfunction "1_1") (pintype "passive"))
      (node (ref "HP2") (pin "2") (pinfunction "2_2") (pintype "passive"))
      (node (ref "U1") (pin "11") (pinfunction "PC3/SPI2_MOSI_11") (pintype "bidirectional"))
    )
    (net (code "25") (name "/RF") (class "Default")
      (node (ref "CHP1") (pin "1") (pinfunction "1_1") (pintype "passive"))
      (node (ref "HP1") (pin "2") (pinfunction "2_2") (pintype "passive"))
      (node (ref "U1") (pin "10") (pinfunction "PC2/SPI2_MISO_10") (pintype "bidirectional"))
    )
    (net (code "26") (name "/RF_EM") (class "Default")
      (node (ref "Q2") (pin "1") (pinfunction "G_1") (pintype "passive"))
      (node (ref "R_IR2") (pin "2") (pinfunction "2_2") (pintype "passive"))
      (node (ref "U1") (pin "45") (pinfunction "PA12_45") (pintype "bidirectional"))
    )
    (net (code "27") (name "/RF_RV") (class "Default")
      (node (ref "CHP1") (pin "2") (pinfunction "2_2") (pintype "passive"))
      (node (ref "RF_RV") (pin "2") (pinfunction "2_2") (pintype "passive"))
      (node (ref "R_IR7") (pin "2") (pinfunction "2_2") (pintype "passive"))
    )
    (net (code "28") (name "/RX") (class "Default")
      (node (ref "P1") (pin "4") (pinfunction "4_4") (pintype "passive"))
      (node (ref "U1") (pin "52") (pinfunction "PC11_52") (pintype "bidirectional"))
    )
    (net (code "29") (name "/R_RV") (class "Default")
      (node (ref "CHP2") (pin "2") (pinfunction "2_2") (pintype "passive"))
      (node (ref "R_IR8") (pin "2") (pinfunction "2_2") (pintype "passive"))
      (node (ref "R_RV") (pin "2") (pinfunction "2_2") (pintype "passive"))
    )
    (net (code "30") (name "/SCK") (class "Default")
      (node (ref "U") (pin "13") (pinfunction "SCX_13") (pintype "input"))
      (node (ref "U1") (pin "21") (pinfunction "PA5/SPI1_SCK_21") (pintype "bidirectional"))
    )
    (net (code "31") (name "/SCL_LED") (class "Default")
      (node (ref "J3") (pin "02") (pinfunction "02_02") (pintype "passive"))
      (node (ref "U1") (pin "58") (pinfunction "PB6_58") (pintype "bidirectional"))
    )
    (net (code "32") (name "/SCL_enA") (class "Default")
      (node (ref "J3_A") (pin "02") (pinfunction "02_02") (pintype "passive"))
      (node (ref "U1") (pin "41") (pinfunction "PA8_41") (pintype "bidirectional"))
    )
    (net (code "33") (name "/SCL_enB") (class "Default")
      (node (ref "J3_B") (pin "02") (pinfunction "02_02") (pintype "passive"))
      (node (ref "U1") (pin "29") (pinfunction "PB10_29") (pintype "bidirectional"))
    )
    (net (code "34") (name "/SDA_LED") (class "Default")
      (node (ref "J3") (pin "01") (pinfunction "01_01") (pintype "passive"))
      (node (ref "U1") (pin "59") (pinfunction "PB7_59") (pintype "bidirectional"))
    )
    (net (code "35") (name "/SDA_enA") (class "Default")
      (node (ref "J3_A") (pin "01") (pinfunction "01_01") (pintype "passive"))
      (node (ref "U1") (pin "40") (pinfunction "PC9_40") (pintype "bidirectional"))
    )
    (net (code "36") (name "/SDA_enB") (class "Default")
      (node (ref "J3_B") (pin "01") (pinfunction "01_01") (pintype "passive"))
      (node (ref "U1") (pin "30") (pinfunction "PB11_30") (pintype "bidirectional"))
    )
    (net (code "37") (name "/SWCLK") (class "Default")
      (node (ref "P0") (pin "03") (pinfunction "03_03") (pintype "passive"))
      (node (ref "U1") (pin "49") (pinfunction "PA14/JTCK-SWCLK_49") (pintype "bidirectional"))
    )
    (net (code "38") (name "/SWDIO") (class "Default")
      (node (ref "P0") (pin "02") (pinfunction "02_02") (pintype "passive"))
      (node (ref "U1") (pin "46") (pinfunction "PA13/JMS-SWDIO_46") (pintype "bidirectional"))
    )
    (net (code "39") (name "/TX") (class "Default")
      (node (ref "P1") (pin "3") (pinfunction "3_3") (pintype "passive"))
      (node (ref "R_TX") (pin "1") (pinfunction "1_1") (pintype "passive"))
      (node (ref "U1") (pin "51") (pinfunction "PC10_51") (pintype "bidirectional"))
    )
    (net (code "40") (name "/TX_LED") (class "Default")
      (node (ref "LED_TX") (pin "1") (pinfunction "C_1") (pintype "passive"))
      (node (ref "Q4") (pin "3") (pinfunction "D_3") (pintype "passive"))
    )
    (net (code "41") (name "GND") (class "Default")
      (node (ref "C1") (pin "1") (pinfunction "1_1") (pintype "passive"))
      (node (ref "C10") (pin "2") (pinfunction "2_2") (pintype "passive"))
      (node (ref "C11") (pin "2") (pinfunction "2_2") (pintype "passive"))
      (node (ref "C12") (pin "2") (pinfunction "2_2") (pintype "passive"))
      (node (ref "C13") (pin "2") (pinfunction "2_2") (pintype "passive"))
      (node (ref "C16") (pin "2") (pinfunction "2_2") (pintype "passive"))
      (node (ref "C17") (pin "2") (pinfunction "2_2") (pintype "passive"))
      (node (ref "C18") (pin "2") (pinfunction "2_2") (pintype "passive"))
      (node (ref "C19") (pin "1") (pinfunction "C_1") (pintype "passive"))
      (node (ref "C2") (pin "1") (pinfunction "1_1") (pintype "passive"))
      (node (ref "C21") (pin "2") (pinfunction "2_2") (pintype "passive"))
      (node (ref "C22") (pin "1") (pinfunction "1_1") (pintype "passive"))
      (node (ref "C23") (pin "2") (pinfunction "2_2") (pintype "passive"))
      (node (ref "C24") (pin "2") (pinfunction "2_2") (pintype "passive"))
      (node (ref "C3") (pin "2") (pinfunction "2_2") (pintype "passive"))
      (node (ref "C4") (pin "2") (pinfunction "2_2") (pintype "passive"))
      (node (ref "C5") (pin "2") (pinfunction "2_2") (pintype "passive"))
      (node (ref "C6") (pin "2") (pinfunction "2_2") (pintype "passive"))
      (node (ref "C7") (pin "2") (pinfunction "2_2") (pintype "passive"))
      (node (ref "C8") (pin "2") (pinfunction "2_2") (pintype "passive"))
      (node (ref "C9") (pin "2") (pinfunction "2_2") (pintype "passive"))
      (node (ref "C_IR1") (pin "1") (pinfunction "1_1") (pintype "passive"))
      (node (ref "C_IR2") (pin "2") (pinfunction "2_2") (pintype "passive"))
      (node (ref "C_IR3") (pin "1") (pinfunction "1_1") (pintype "passive"))
      (node (ref "C_IR4") (pin "2") (pinfunction "2_2") (pintype "passive"))
      (node (ref "C_IR5") (pin "2") (pinfunction "2_2") (pintype "passive"))
      (node (ref "C_IR6") (pin "1") (pinfunction "1_1") (pintype "passive"))
      (node (ref "C_MPU1") (pin "2") (pinfunction "2_2") (pintype "passive"))
      (node (ref "C_MPU2") (pin "2") (pinfunction "2_2") (pintype "passive"))
      (node (ref "D1") (pin "1") (pinfunction "C_1") (pintype "passive"))
      (node (ref "D13") (pin "1") (pinfunction "C_1") (pintype "passive"))
      (node (ref "D3") (pin "1") (pinfunction "C_1") (pintype "passive"))
      (node (ref "D5") (pin "1") (pinfunction "C_1") (pintype "passive"))
      (node (ref "D6") (pin "1") (pinfunction "C_1") (pintype "passive"))
      (node (ref "HP1") (pin "1") (pinfunction "1_1") (pintype "passive"))
      (node (ref "HP2") (pin "1") (pinfunction "1_1") (pintype "passive"))
      (node (ref "HP3") (pin "1") (pinfunction "1_1") (pintype "passive"))
      (node (ref "HP4") (pin "1") (pinfunction "1_1") (pintype "passive"))
      (node (ref "J3") (pin "04") (pinfunction "04_04") (pintype "passive"))
      (node (ref "J3_A") (pin "04") (pinfunction "04_04") (pintype "passive"))
      (node (ref "J3_B") (pin "04") (pinfunction "04_04") (pintype "passive"))
      (node (ref "P0") (pin "04") (pinfunction "04_04") (pintype "passive"))
      (node (ref "P1") (pin "2") (pinfunction "2_2") (pintype "passive"))
      (node (ref "P3") (pin "2") (pinfunction "2_2") (pintype "passive"))
      (node (ref "Q1") (pin "2") (pinfunction "S_2") (pintype "passive"))
      (node (ref "Q2") (pin "2") (pinfunction "S_2") (pintype "passive"))
      (node (ref "Q3") (pin "2") (pinfunction "S_2") (pintype "passive"))
      (node (ref "Q4") (pin "2") (pinfunction "S_2") (pintype "passive"))
      (node (ref "Q5") (pin "2") (pinfunction "S_2") (pintype "passive"))
      (node (ref "R12") (pin "2") (pinfunction "2_2") (pintype "passive"))
      (node (ref "R5") (pin "1") (pinfunction "1_1") (pintype "passive"))
      (node (ref "R7") (pin "1") (pinfunction "1_1") (pintype "passive"))
      (node (ref "RB0") (pin "1") (pinfunction "1_1") (pintype "passive"))
      (node (ref "RB1") (pin "2") (pinfunction "2_2") (pintype "passive"))
      (node (ref "RST") (pin "2") (pinfunction "2_2") (pintype "passive"))
      (node (ref "R_BT02") (pin "1") (pinfunction "1_1") (pintype "passive"))
      (node (ref "R_BT1") (pin "1") (pinfunction "1_1") (pintype "passive"))
      (node (ref "R_BUZZ") (pin "1") (pinfunction "1_1") (pintype "passive"))
      (node (ref "R_IR1") (pin "1") (pinfunction "1_1") (pintype "passive"))
      (node (ref "R_IR10") (pin "1") (pinfunction "1_1") (pintype "passive"))
      (node (ref "R_IR2") (pin "1") (pinfunction "1_1") (pintype "passive"))
      (node (ref "R_IR3") (pin "1") (pinfunction "1_1") (pintype "passive"))
      (node (ref "R_IR7") (pin "1") (pinfunction "1_1") (pintype "passive"))
      (node (ref "R_IR8") (pin "1") (pinfunction "1_1") (pintype "passive"))
      (node (ref "R_IR9") (pin "1") (pinfunction "1_1") (pintype "passive"))
      (node (ref "U") (pin "6") (pinfunction "GNDIO_6") (pintype "power_in"))
      (node (ref "U") (pin "7") (pinfunction "GND_7") (pintype "power_in"))
      (node (ref "U1") (pin "12") (pinfunction "VSSA_12") (pintype "power_in"))
      (node (ref "U1") (pin "18") (pinfunction "VSS_18") (pintype "power_in"))
      (node (ref "U1") (pin "63") (pinfunction "VSS_63") (pintype "power_in"))
      (node (ref "U2") (pin "1") (pinfunction "GND_1") (pintype "power_in"))
      (node (ref "U3") (pin "4") (pinfunction "GND_4") (pintype "power_in"))
      (node (ref "U5") (pin "13") (pinfunction "GND_13") (pintype "power_in"))
      (node (ref "U5") (pin "17") (pinfunction "GND_17") (pintype "power_in"))
      (node (ref "U6") (pin "1") (pinfunction "GND_1") (pintype "power_in"))
      (node (ref "Y1") (pin "2") (pinfunction "GND_2") (pintype "power_in"))
      (node (ref "Y1") (pin "4") (pinfunction "GND_4") (pintype "power_in"))
    )
    (net (code "42") (name "Net-(C14-Pad2)") (class "Default")
      (node (ref "C14") (pin "2") (pinfunction "2_2") (pintype "passive"))
      (node (ref "R5") (pin "2") (pinfunction "2_2") (pintype "passive"))
    )
    (net (code "43") (name "Net-(D1-A)") (class "Default")
      (node (ref "D1") (pin "2") (pinfunction "A_2") (pintype "passive"))
      (node (ref "R3") (pin "2") (pinfunction "2_2") (pintype "passive"))
    )
    (net (code "44") (name "Net-(D3-A)") (class "Default")
      (node (ref "D3") (pin "2") (pinfunction "A_2") (pintype "passive"))
      (node (ref "R10") (pin "2") (pinfunction "2_2") (pintype "passive"))
    )
    (net (code "45") (name "Net-(D4-A)") (class "Default")
      (node (ref "D4") (pin "2") (pinfunction "A_2") (pintype "passive"))
      (node (ref "LS1") (pin "1") (pinfunction "C_1") (pintype "passive"))
      (node (ref "Q5") (pin "3") (pinfunction "D_3") (pintype "passive"))
    )
    (net (code "46") (name "Net-(D5-A)") (class "Default")
      (node (ref "D5") (pin "2") (pinfunction "A_2") (pintype "passive"))
      (node (ref "R_DBL1") (pin "2") (pinfunction "2_2") (pintype "passive"))
    )
    (net (code "47") (name "Net-(D6-A)") (class "Default")
      (node (ref "D6") (pin "2") (pinfunction "A_2") (pintype "passive"))
      (node (ref "R_DBL2") (pin "2") (pinfunction "2_2") (pintype "passive"))
    )
    (net (code "48") (name "Net-(D13-A)") (class "Default")
      (node (ref "D13") (pin "2") (pinfunction "A_2") (pintype "passive"))
      (node (ref "R13") (pin "2") (pinfunction "2_2") (pintype "passive"))
    )
    (net (code "49") (name "Net-(LED_TX-A)") (class "Default")
      (node (ref "LED_TX") (pin "2") (pinfunction "A_2") (pintype "passive"))
      (node (ref "R_TXLED") (pin "2") (pinfunction "2_2") (pintype "passive"))
    )
    (net (code "50") (name "Net-(LF_IR-Pad1)") (class "Default")
      (node (ref "LF_IR") (pin "1") (pinfunction "1_1") (pintype "passive"))
      (node (ref "R_IR6") (pin "2") (pinfunction "2_2") (pintype "passive"))
    )
    (net (code "51") (name "Net-(L_IR-Pad1)") (class "Default")
      (node (ref "L_IR") (pin "1") (pinfunction "1_1") (pintype "passive"))
      (node (ref "R_IR") (pin "2") (pinfunction "2_2") (pintype "passive"))
    )
    (net (code "52") (name "Net-(Q1-D)") (class "Default")
      (node (ref "Q1") (pin "3") (pinfunction "D_3") (pintype "passive"))
      (node (ref "R_IR4") (pin "1") (pinfunction "1_1") (pintype "passive"))
    )
    (net (code "53") (name "Net-(Q2-D)") (class "Default")
      (node (ref "Q2") (pin "3") (pinfunction "D_3") (pintype "passive"))
      (node (ref "R_IR5") (pin "1") (pinfunction "1_1") (pintype "passive"))
    )
    (net (code "54") (name "Net-(Q3-D)") (class "Default")
      (node (ref "Q3") (pin "3") (pinfunction "D_3") (pintype "passive"))
      (node (ref "R_IR6") (pin "1") (pinfunction "1_1") (pintype "passive"))
    )
    (net (code "55") (name "Net-(Q4-G)") (class "Default")
      (node (ref "Q4") (pin "1") (pinfunction "G_1") (pintype "passive"))
      (node (ref "R_TX") (pin "2") (pinfunction "2_2") (pintype "passive"))
    )
    (net (code "56") (name "Net-(RF_IR-Pad1)") (class "Default")
      (node (ref "RF_IR") (pin "1") (pinfunction "1_1") (pintype "passive"))
      (node (ref "R_IR5") (pin "2") (pinfunction "2_2") (pintype "passive"))
    )
    (net (code "57") (name "Net-(R_IR-Pad1)") (class "Default")
      (node (ref "R_IR") (pin "1") (pinfunction "1_1") (pintype "passive"))
      (node (ref "R_IR4") (pin "2") (pinfunction "2_2") (pintype "passive"))
    )
    (net (code "58") (name "Net-(SW0-COM)") (class "Default")
      (node (ref "P3") (pin "1") (pinfunction "1_1") (pintype "passive"))
      (node (ref "SW0") (pin "2") (pinfunction "COM_2") (pintype "passive"))
    )
    (net (code "59") (name "Net-(U-VDD)") (class "Default")
      (node (ref "C_MPU2") (pin "1") (pinfunction "1_1") (pintype "passive"))
      (node (ref "U") (pin "8") (pinfunction "VDD_8") (pintype "power_in"))
    )
    (net (code "60") (name "Net-(U-VDDIO)") (class "Default")
      (node (ref "C_MPU1") (pin "1") (pinfunction "1_1") (pintype "passive"))
      (node (ref "U") (pin "5") (pinfunction "VDDIO_5") (pintype "power_in"))
    )
    (net (code "61") (name "Net-(U1-BOOT0)") (class "Default")
      (node (ref "RB0") (pin "2") (pinfunction "2_2") (pintype "passive"))
      (node (ref "U1") (pin "60") (pinfunction "BOOT0_60") (pintype "bidirectional"))
    )
    (net (code "62") (name "Net-(U1-NRST)") (class "Default")
      (node (ref "C3") (pin "1") (pinfunction "1_1") (pintype "passive"))
      (node (ref "R2") (pin "2") (pinfunction "2_2") (pintype "passive"))
      (node (ref "RST") (pin "1") (pinfunction "1_1") (pintype "passive"))
      (node (ref "U1") (pin "7") (pinfunction "NRST_7") (pintype "bidirectional"))
    )
    (net (code "63") (name "Net-(U1-PH0{slash}OSC_IN)") (class "Default")
      (node (ref "C1") (pin "2") (pinfunction "2_2") (pintype "passive"))
      (node (ref "U1") (pin "5") (pinfunction "PH0/OSC_IN_5") (pintype "bidirectional"))
      (node (ref "Y1") (pin "1") (pinfunction "1_1") (pintype "passive"))
    )
    (net (code "64") (name "Net-(U1-PH1{slash}OSC_OUT)") (class "Default")
      (node (ref "C2") (pin "2") (pinfunction "2_2") (pintype "passive"))
      (node (ref "U1") (pin "6") (pinfunction "PH1/OSC_OUT_6") (pintype "bidirectional"))
      (node (ref "Y1") (pin "3") (pinfunction "3_3") (pintype "passive"))
    )
    (net (code "65") (name "Net-(U1-VCAP_1)") (class "Default")
      (node (ref "C4") (pin "1") (pinfunction "1_1") (pintype "passive"))
      (node (ref "U1") (pin "31") (pinfunction "VCAP_1_31") (pintype "power_in"))
    )
    (net (code "66") (name "Net-(U1-VCAP_2)") (class "Default")
      (node (ref "C5") (pin "1") (pinfunction "1_1") (pintype "passive"))
      (node (ref "U1") (pin "47") (pinfunction "VCAP_2_47") (pintype "power_in"))
    )
    (net (code "67") (name "Net-(U3-BS)") (class "Default")
      (node (ref "C15") (pin "1") (pinfunction "1_1") (pintype "passive"))
      (node (ref "U3") (pin "1") (pinfunction "BS_1") (pintype "passive"))
    )
    (net (code "68") (name "Net-(U3-COMP)") (class "Default")
      (node (ref "C14") (pin "1") (pinfunction "1_1") (pintype "passive"))
      (node (ref "U3") (pin "6") (pinfunction "COMP_6") (pintype "passive"))
    )
    (net (code "69") (name "Net-(U3-EN)") (class "Default")
      (node (ref "R33") (pin "2") (pinfunction "2_2") (pintype "passive"))
      (node (ref "U3") (pin "7") (pinfunction "EN_7") (pintype "input"))
    )
    (net (code "70") (name "Net-(U3-FB)") (class "Default")
      (node (ref "R7") (pin "2") (pinfunction "2_2") (pintype "passive"))
      (node (ref "R8") (pin "2") (pinfunction "2_2") (pintype "passive"))
      (node (ref "U3") (pin "5") (pinfunction "FB_5") (pintype "input"))
    )
    (net (code "71") (name "Net-(U3-SS)") (class "Default")
      (node (ref "C13") (pin "1") (pinfunction "1_1") (pintype "passive"))
      (node (ref "U3") (pin "8") (pinfunction "SS_8") (pintype "passive"))
    )
    (net (code "72") (name "Net-(U3-SW)") (class "Default")
      (node (ref "C15") (pin "2") (pinfunction "2_2") (pintype "passive"))
      (node (ref "L3") (pin "1") (pinfunction "1_1") (pintype "passive"))
      (node (ref "U3") (pin "3") (pinfunction "SW_3") (pintype "output"))
    )
    (net (code "73") (name "Net-(U5-AISEN)") (class "Default")
      (node (ref "R12") (pin "1") (pinfunction "1_1") (pintype "passive"))
      (node (ref "U5") (pin "3") (pinfunction "AISEN_3") (pintype "input"))
      (node (ref "U5") (pin "6") (pinfunction "BISEN_6") (pintype "input"))
    )
    (net (code "74") (name "Net-(U5-VCP)") (class "Default")
      (node (ref "C20") (pin "2") (pinfunction "2_2") (pintype "passive"))
      (node (ref "U5") (pin "11") (pinfunction "VCP_11") (pintype "passive"))
    )
    (net (code "75") (name "Net-(U5-VINT)") (class "Default")
      (node (ref "C21") (pin "1") (pinfunction "1_1") (pintype "passive"))
      (node (ref "U5") (pin "14") (pinfunction "VINT_14") (pintype "power_in"))
    )
    (net (code "76") (name "Net-(U5-~{SLEEP})") (class "Default")
      (node (ref "R11") (pin "2") (pinfunction "2_2") (pintype "passive"))
      (node (ref "U5") (pin "1") (pinfunction "~{SLEEP}_1") (pintype "input"))
    )
    (net (code "77") (name "V33") (class "Default")
      (node (ref "C24") (pin "1") (pinfunction "1_1") (pintype "passive"))
      (node (ref "C_DB1") (pin "1") (pinfunction "1_1") (pintype "passive"))
      (node (ref "C_DB2") (pin "1") (pinfunction "1_1") (pintype "passive"))
      (node (ref "D4") (pin "1") (pinfunction "C_1") (pintype "passive"))
      (node (ref "DEBUG_1") (pin "2") (pinfunction "2_2") (pintype "passive"))
      (node (ref "DEBUG_2") (pin "2") (pinfunction "2_2") (pintype "passive"))
      (node (ref "J3") (pin "03") (pinfunction "03_03") (pintype "passive"))
      (node (ref "J3_A") (pin "05") (pinfunction "05_05") (pintype "passive"))
      (node (ref "J3_B") (pin "05") (pinfunction "05_05") (pintype "passive"))
      (node (ref "LF_RV") (pin "1") (pinfunction "1_1") (pintype "passive"))
      (node (ref "LS1") (pin "2") (pinfunction "A_2") (pintype "passive"))
      (node (ref "L_RV") (pin "1") (pinfunction "1_1") (pintype "passive"))
      (node (ref "R13") (pin "1") (pinfunction "1_1") (pintype "passive"))
      (node (ref "RF_RV") (pin "1") (pinfunction "1_1") (pintype "passive"))
      (node (ref "R_RV") (pin "1") (pinfunction "1_1") (pintype "passive"))
      (node (ref "R_TXLED") (pin "1") (pinfunction "1_1") (pintype "passive"))
      (node (ref "U6") (pin "2") (pinfunction "OUT_2") (pintype "power_in"))
      (node (ref "U6") (pin "4") (pinfunction "TAB_4") (pintype "power_in"))
    )
    (net (code "78") (name "VDD33") (class "Default")
      (node (ref "C11") (pin "1") (pinfunction "1_1") (pintype "passive"))
      (node (ref "C6") (pin "1") (pinfunction "1_1") (pintype "passive"))
      (node (ref "C7") (pin "1") (pinfunction "1_1") (pintype "passive"))
      (node (ref "C8") (pin "1") (pinfunction "1_1") (pintype "passive"))
      (node (ref "C9") (pin "1") (pinfunction "1_1") (pintype "passive"))
      (node (ref "FB1") (pin "1") (pinfunction "1_1") (pintype "passive"))
      (node (ref "R2") (pin "1") (pinfunction "1_1") (pintype "passive"))
      (node (ref "R3") (pin "1") (pinfunction "1_1") (pintype "passive"))
      (node (ref "R_MCU") (pin "2") (pinfunction "2_2") (pintype "passive"))
      (node (ref "U1") (pin "1") (pinfunction "VBAT_1") (pintype "power_in"))
      (node (ref "U1") (pin "19") (pinfunction "VDD_19") (pintype "power_in"))
      (node (ref "U1") (pin "32") (pinfunction "VDD_32") (pintype "power_in"))
      (node (ref "U1") (pin "48") (pinfunction "VDD_48") (pintype "power_in"))
      (node (ref "U1") (pin "64") (pinfunction "VDD_64") (pintype "power_in"))
    )
    (net (code "79") (name "VDD33_OUT") (class "Default")
      (node (ref "C18") (pin "1") (pinfunction "1_1") (pintype "passive"))
      (node (ref "R_MCU") (pin "1") (pinfunction "1_1") (pintype "passive"))
      (node (ref "U2") (pin "2") (pinfunction "OUT_2") (pintype "power_in"))
      (node (ref "U2") (pin "4") (pinfunction "TAB_4") (pintype "power_in"))
    )
    (net (code "80") (name "VDDA") (class "Default")
      (node (ref "C10") (pin "1") (pinfunction "1_1") (pintype "passive"))
      (node (ref "C22") (pin "2") (pinfunction "2_2") (pintype "passive"))
      (node (ref "FB1") (pin "2") (pinfunction "2_2") (pintype "passive"))
      (node (ref "U1") (pin "13") (pinfunction "VDDA_13") (pintype "power_in"))
    )
    (net (code "81") (name "VIN74") (class "Default")
      (node (ref "C12") (pin "1") (pinfunction "1_1") (pintype "passive"))
      (node (ref "R33") (pin "1") (pinfunction "1_1") (pintype "passive"))
      (node (ref "SW0") (pin "3") (pinfunction "3_3") (pintype "passive"))
      (node (ref "U3") (pin "2") (pinfunction "IN_2") (pintype "input"))
    )
    (net (code "82") (name "VM") (class "Default")
      (node (ref "C16") (pin "1") (pinfunction "1_1") (pintype "passive"))
      (node (ref "D") (pin "1") (pinfunction "A_1") (pintype "passive"))
      (node (ref "L3") (pin "2") (pinfunction "2_2") (pintype "passive"))
      (node (ref "R8") (pin "1") (pinfunction "1_1") (pintype "passive"))
    )
    (net (code "83") (name "VOUT5") (class "Default")
      (node (ref "C17") (pin "1") (pinfunction "1_1") (pintype "passive"))
      (node (ref "C19") (pin "2") (pinfunction "A_2") (pintype "passive"))
      (node (ref "C20") (pin "1") (pinfunction "1_1") (pintype "passive"))
      (node (ref "C23") (pin "1") (pinfunction "1_1") (pintype "passive"))
      (node (ref "C_IR1") (pin "2") (pinfunction "2_2") (pintype "passive"))
      (node (ref "C_IR2") (pin "1") (pinfunction "1_1") (pintype "passive"))
      (node (ref "C_IR3") (pin "2") (pinfunction "2_2") (pintype "passive"))
      (node (ref "C_IR4") (pin "1") (pinfunction "1_1") (pintype "passive"))
      (node (ref "C_IR5") (pin "1") (pinfunction "1_1") (pintype "passive"))
      (node (ref "C_IR6") (pin "2") (pinfunction "2_2") (pintype "passive"))
      (node (ref "D") (pin "2") (pinfunction "K_2") (pintype "passive"))
      (node (ref "LF_IR") (pin "2") (pinfunction "2_2") (pintype "passive"))
      (node (ref "L_IR") (pin "2") (pinfunction "2_2") (pintype "passive"))
      (node (ref "P0") (pin "01") (pinfunction "01_01") (pintype "passive"))
      (node (ref "P1") (pin "1") (pinfunction "1_1") (pintype "passive"))
      (node (ref "R10") (pin "1") (pinfunction "1_1") (pintype "passive"))
      (node (ref "R11") (pin "1") (pinfunction "1_1") (pintype "passive"))
      (node (ref "RF_IR") (pin "2") (pinfunction "2_2") (pintype "passive"))
      (node (ref "U2") (pin "3") (pinfunction "IN_3") (pintype "power_in"))
      (node (ref "U5") (pin "12") (pinfunction "VM_12") (pintype "power_in"))
      (node (ref "U6") (pin "3") (pinfunction "IN_3") (pintype "power_in"))
    )
    (net (code "84") (name "unconnected-(J3_A-Pad03)") (class "Default")
      (node (ref "J3_A") (pin "03") (pinfunction "03_03") (pintype "passive"))
    )
    (net (code "85") (name "unconnected-(J3_B-Pad03)") (class "Default")
      (node (ref "J3_B") (pin "03") (pinfunction "03_03") (pintype "passive"))
    )
    (net (code "86") (name "unconnected-(SW0-Pad1)") (class "Default")
      (node (ref "SW0") (pin "1") (pinfunction "1_1") (pintype "passive+no_connect"))
    )
    (net (code "87") (name "unconnected-(U-ASCX-Pad3)") (class "Default")
      (node (ref "U") (pin "3") (pinfunction "ASCX_3") (pintype "input+no_connect"))
    )
    (net (code "88") (name "unconnected-(U-ASDX-Pad2)") (class "Default")
      (node (ref "U") (pin "2") (pinfunction "ASDX_2") (pintype "bidirectional+no_connect"))
    )
    (net (code "89") (name "unconnected-(U-INT1-Pad4)") (class "Default")
      (node (ref "U") (pin "4") (pinfunction "INT1_4") (pintype "bidirectional+no_connect"))
    )
    (net (code "90") (name "unconnected-(U-INT2-Pad9)") (class "Default")
      (node (ref "U") (pin "9") (pinfunction "INT2_9") (pintype "bidirectional+no_connect"))
    )
    (net (code "91") (name "unconnected-(U-OSCB-Pad10)") (class "Default")
      (node (ref "U") (pin "10") (pinfunction "OSCB_10") (pintype "bidirectional+no_connect"))
    )
    (net (code "92") (name "unconnected-(U-OSCO-Pad11)") (class "Default")
      (node (ref "U") (pin "11") (pinfunction "OSCO_11") (pintype "bidirectional+no_connect"))
    )
    (net (code "93") (name "unconnected-(U1-PA9-Pad42)") (class "Default")
      (node (ref "U1") (pin "42") (pinfunction "PA9_42") (pintype "bidirectional+no_connect"))
    )
    (net (code "94") (name "unconnected-(U1-PA15-Pad50)") (class "Default")
      (node (ref "U1") (pin "50") (pinfunction "PA15_50") (pintype "bidirectional+no_connect"))
    )
    (net (code "95") (name "unconnected-(U1-PB0-Pad26)") (class "Default")
      (node (ref "U1") (pin "26") (pinfunction "PB0_26") (pintype "bidirectional+no_connect"))
    )
    (net (code "96") (name "unconnected-(U1-PB1-Pad27)") (class "Default")
      (node (ref "U1") (pin "27") (pinfunction "PB1_27") (pintype "bidirectional+no_connect"))
    )
    (net (code "97") (name "unconnected-(U1-PB3-Pad55)") (class "Default")
      (node (ref "U1") (pin "55") (pinfunction "PB3_55") (pintype "bidirectional+no_connect"))
    )
    (net (code "98") (name "unconnected-(U1-PB4-Pad56)") (class "Default")
      (node (ref "U1") (pin "56") (pinfunction "PB4_56") (pintype "bidirectional+no_connect"))
    )
    (net (code "99") (name "unconnected-(U1-PB8-Pad61)") (class "Default")
      (node (ref "U1") (pin "61") (pinfunction "PB8_61") (pintype "bidirectional+no_connect"))
    )
    (net (code "100") (name "unconnected-(U1-PB9-Pad62)") (class "Default")
      (node (ref "U1") (pin "62") (pinfunction "PB9_62") (pintype "bidirectional+no_connect"))
    )
    (net (code "101") (name "unconnected-(U1-PB12-Pad33)") (class "Default")
      (node (ref "U1") (pin "33") (pinfunction "PB12_33") (pintype "bidirectional+no_connect"))
    )
    (net (code "102") (name "unconnected-(U1-PB15-Pad36)") (class "Default")
      (node (ref "U1") (pin "36") (pinfunction "PB15_36") (pintype "bidirectional+no_connect"))
    )
    (net (code "103") (name "unconnected-(U1-PC4-Pad24)") (class "Default")
      (node (ref "U1") (pin "24") (pinfunction "PC4_24") (pintype "bidirectional+no_connect"))
    )
    (net (code "104") (name "unconnected-(U1-PC5-Pad25)") (class "Default")
      (node (ref "U1") (pin "25") (pinfunction "PC5_25") (pintype "bidirectional+no_connect"))
    )
    (net (code "105") (name "unconnected-(U1-PC6-Pad37)") (class "Default")
      (node (ref "U1") (pin "37") (pinfunction "PC6_37") (pintype "bidirectional+no_connect"))
    )
    (net (code "106") (name "unconnected-(U1-PC12-Pad53)") (class "Default")
      (node (ref "U1") (pin "53") (pinfunction "PC12_53") (pintype "bidirectional+no_connect"))
    )
    (net (code "107") (name "unconnected-(U1-PC13{slash}RTC_OUT-Pad2)") (class "Default")
      (node (ref "U1") (pin "2") (pinfunction "PC13/RTC_OUT_2") (pintype "bidirectional+no_connect"))
    )
    (net (code "108") (name "unconnected-(U1-PC14{slash}OSC32_IN-Pad3)") (class "Default")
      (node (ref "U1") (pin "3") (pinfunction "PC14/OSC32_IN_3") (pintype "bidirectional+no_connect"))
    )
    (net (code "109") (name "unconnected-(U1-PC15{slash}OSC32_OUT-Pad4)") (class "Default")
      (node (ref "U1") (pin "4") (pinfunction "PC15/OSC32_OUT_4") (pintype "bidirectional+no_connect"))
    )
    (net (code "110") (name "unconnected-(U1-PD2-Pad54)") (class "Default")
      (node (ref "U1") (pin "54") (pinfunction "PD2_54") (pintype "bidirectional+no_connect"))
    )
    (net (code "111") (name "unconnected-(U3-EP-Pad9)") (class "Default")
      (node (ref "U3") (pin "9") (pinfunction "EP_9") (pintype "power_in+no_connect"))
    )
    (net (code "112") (name "unconnected-(U5-~{FAULT}-Pad8)") (class "Default")
      (node (ref "U5") (pin "8") (pinfunction "~{FAULT}_8") (pintype "open_collector+no_connect"))
    )
  )
)
